# SpeedOfLightController.net
KiCad netlist of a schematic drawn in EAGLE
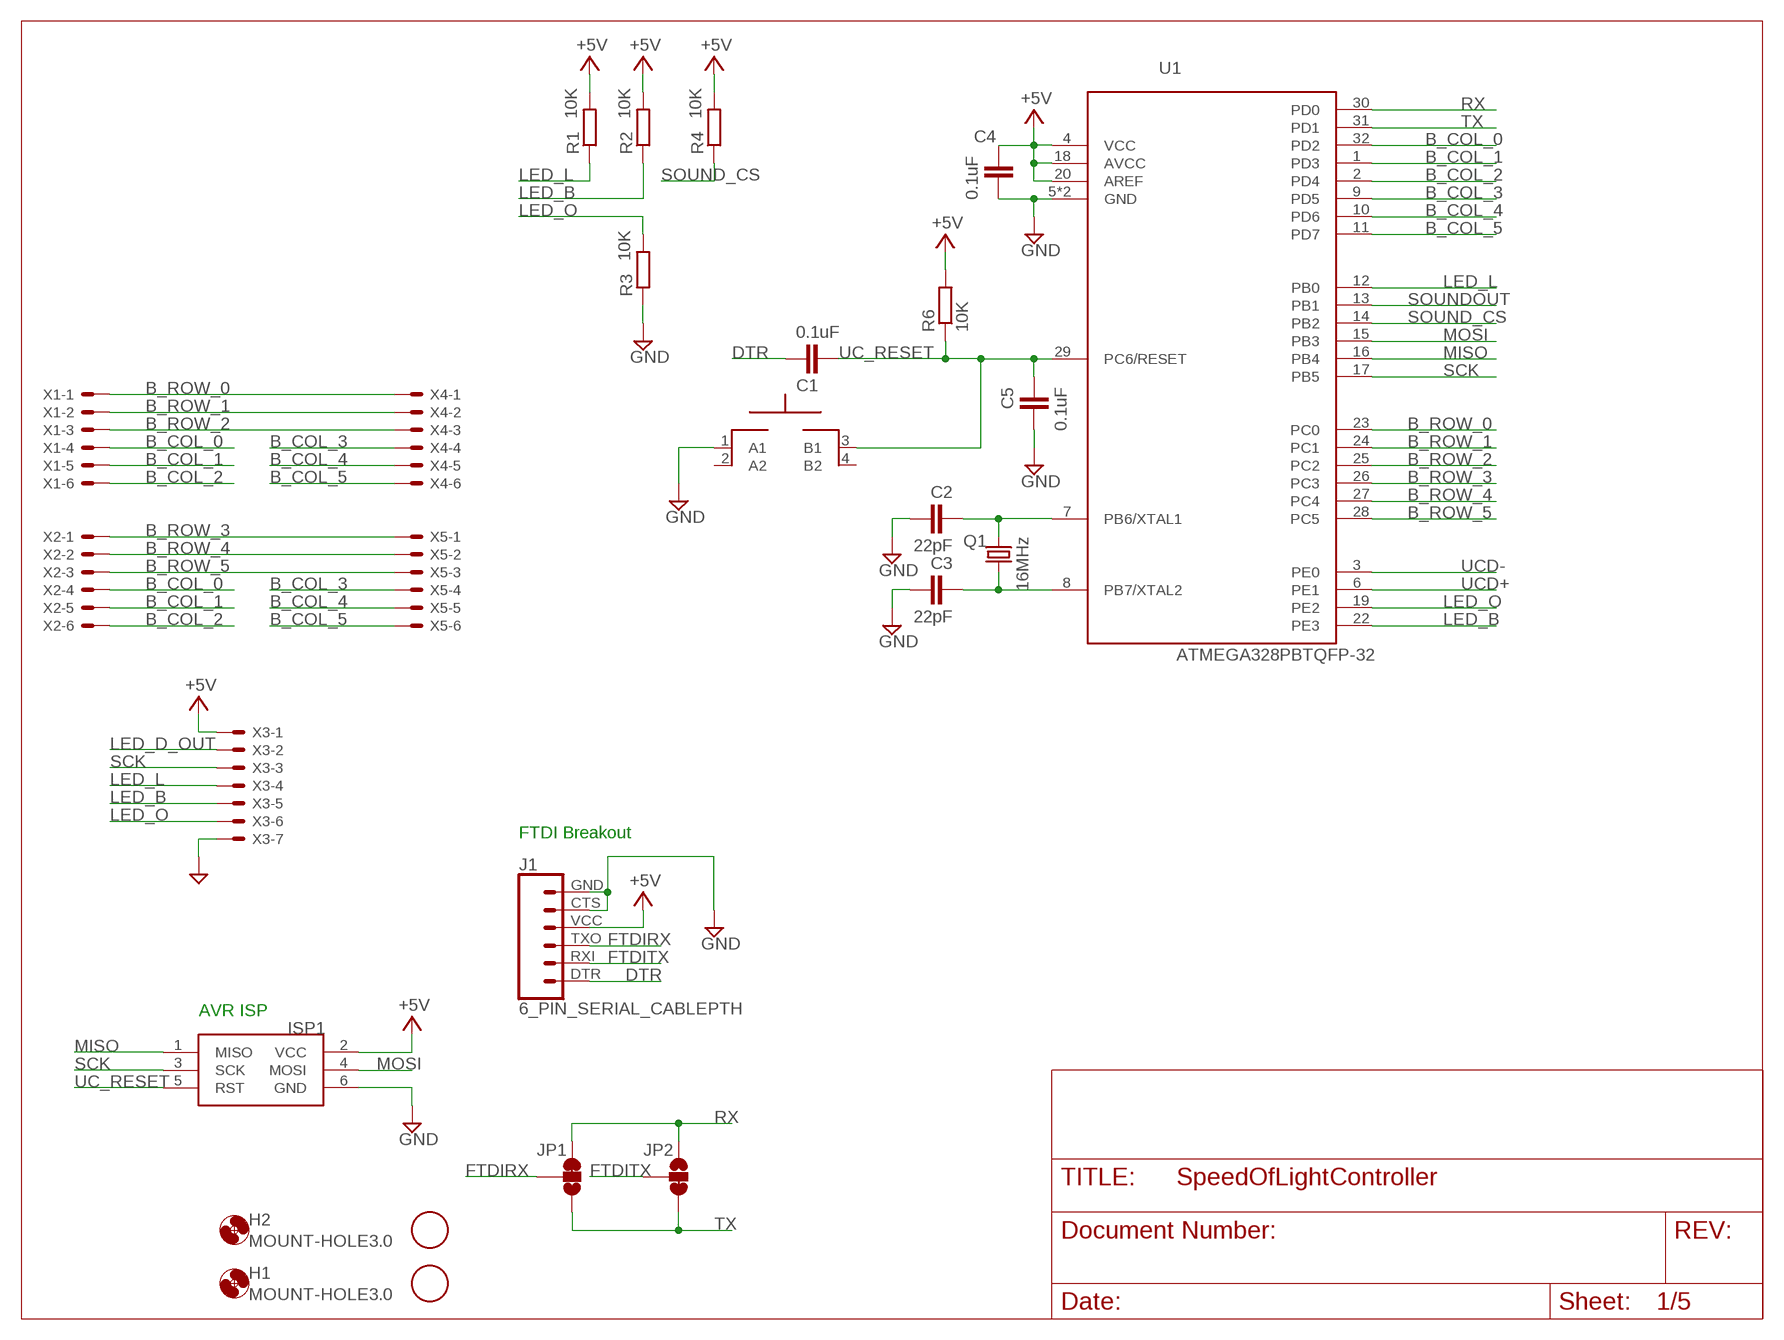
[diagram p0: schematic, sheet 1]
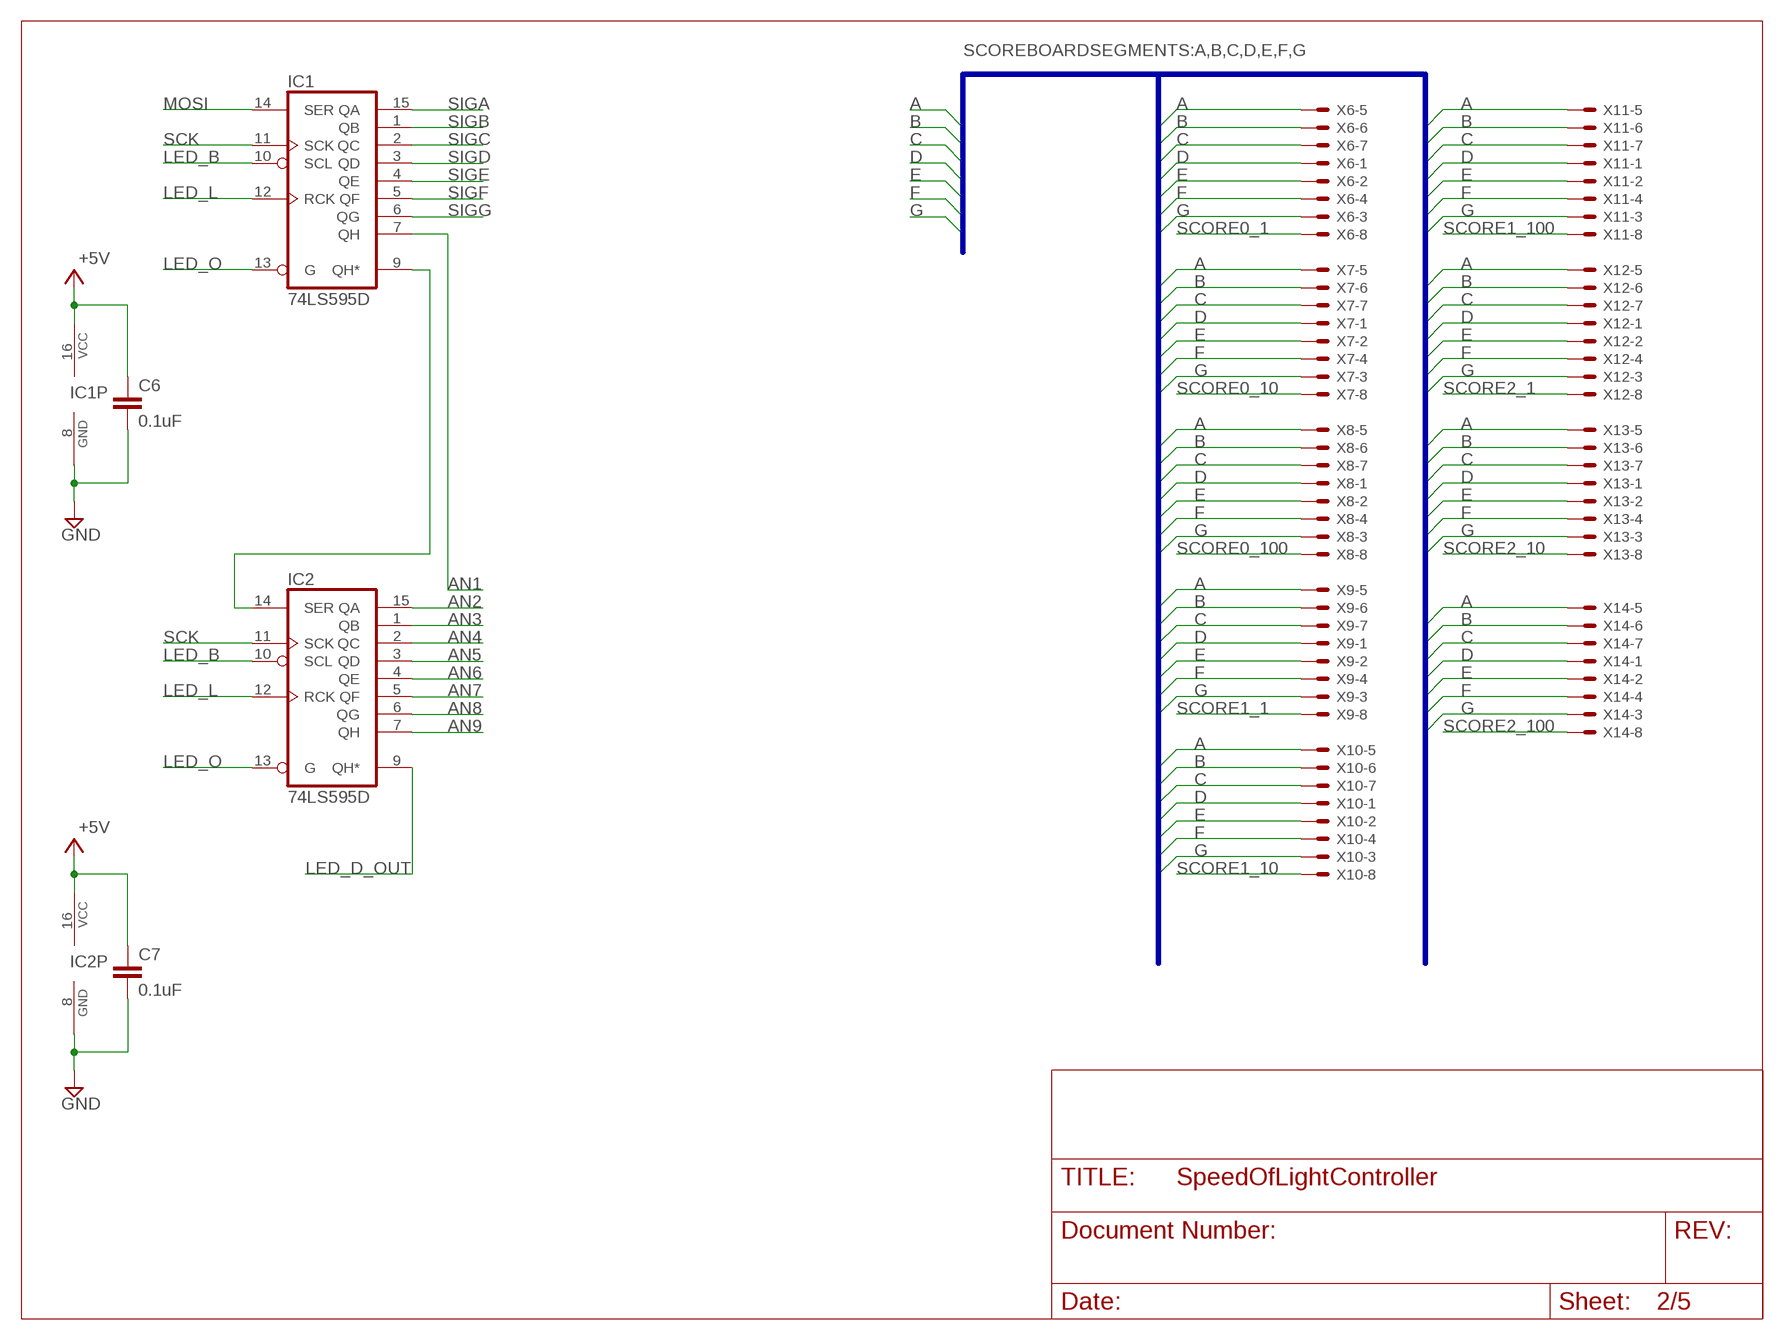
[diagram p1: schematic, sheet 2]
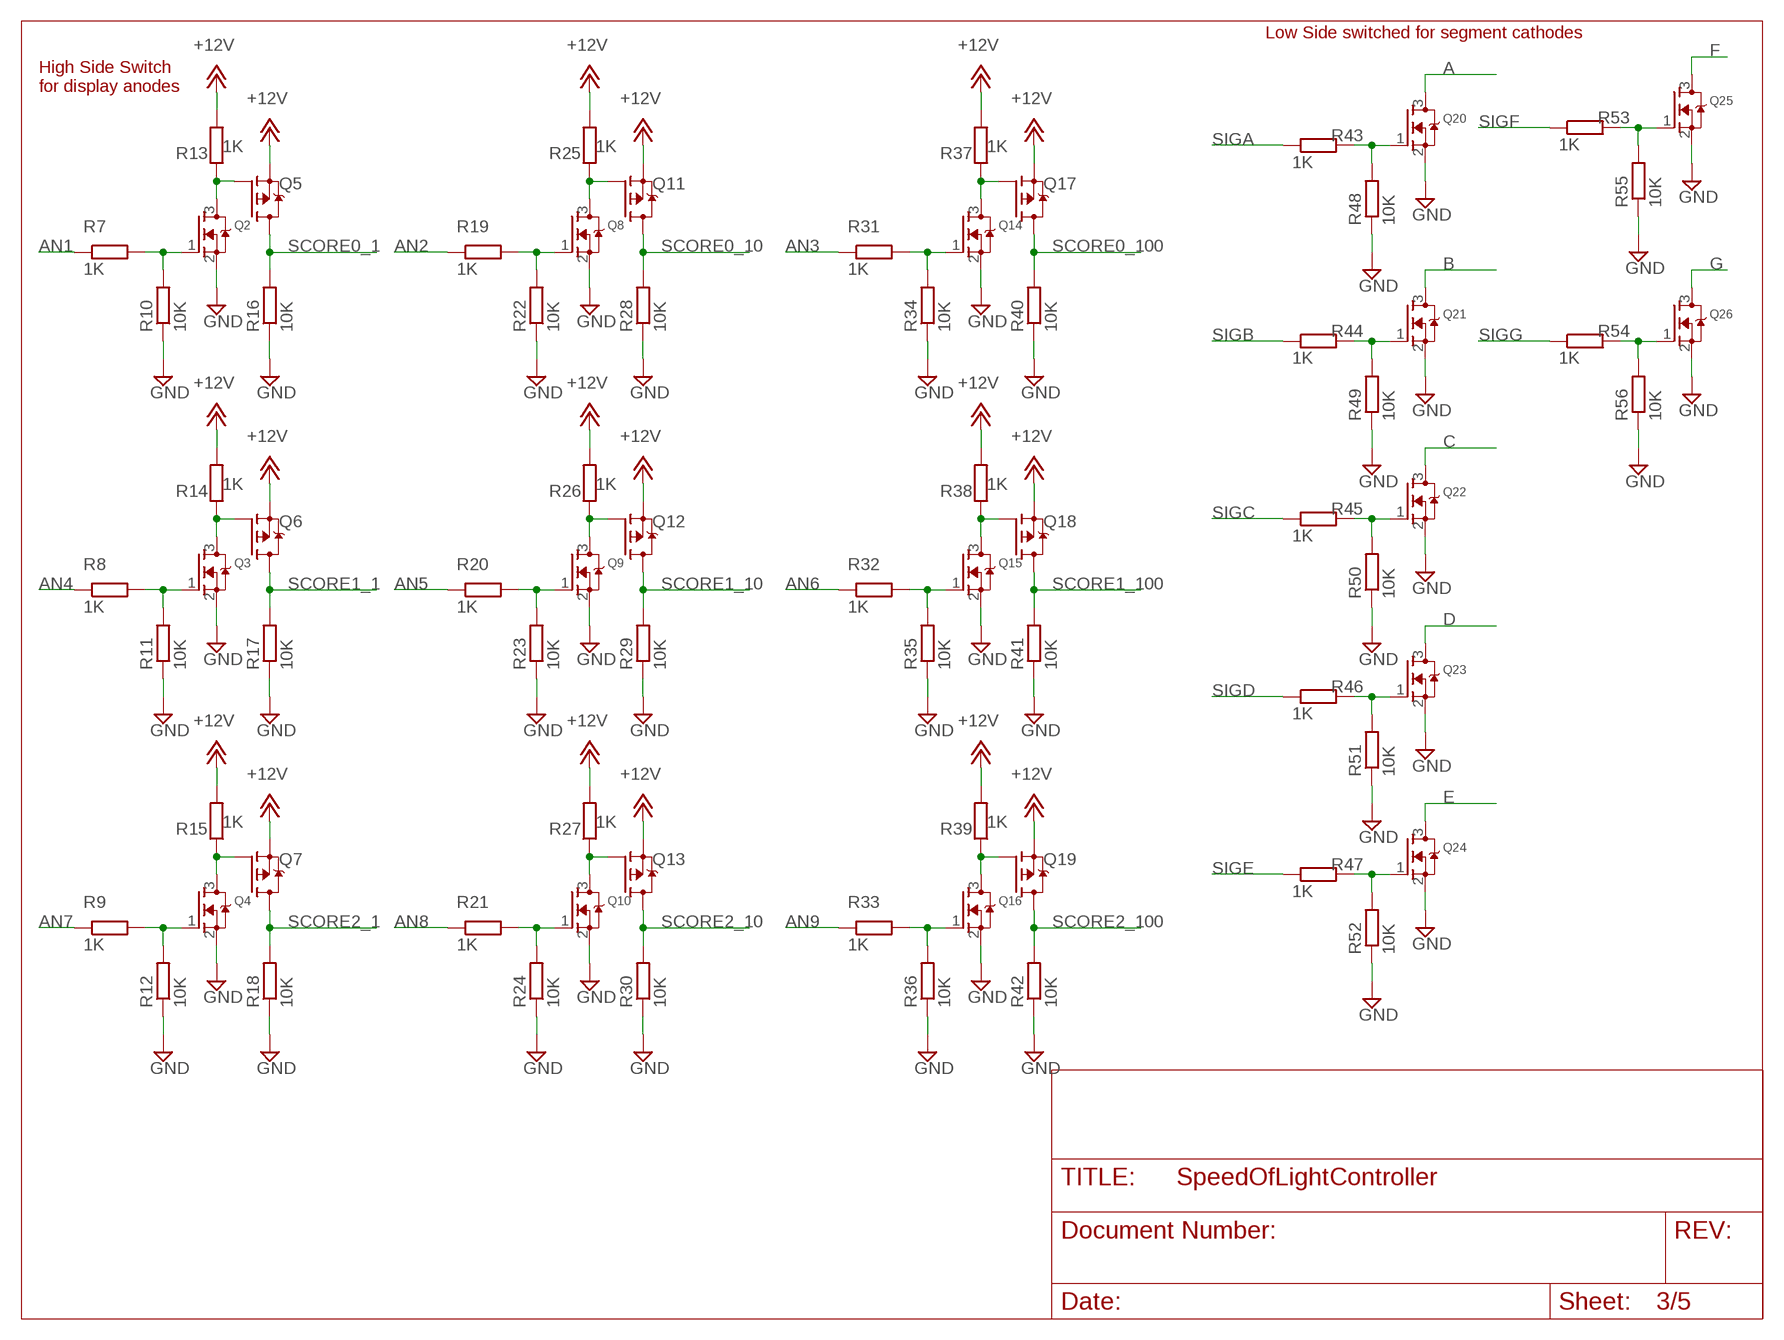
[diagram p2: schematic, sheet 3]
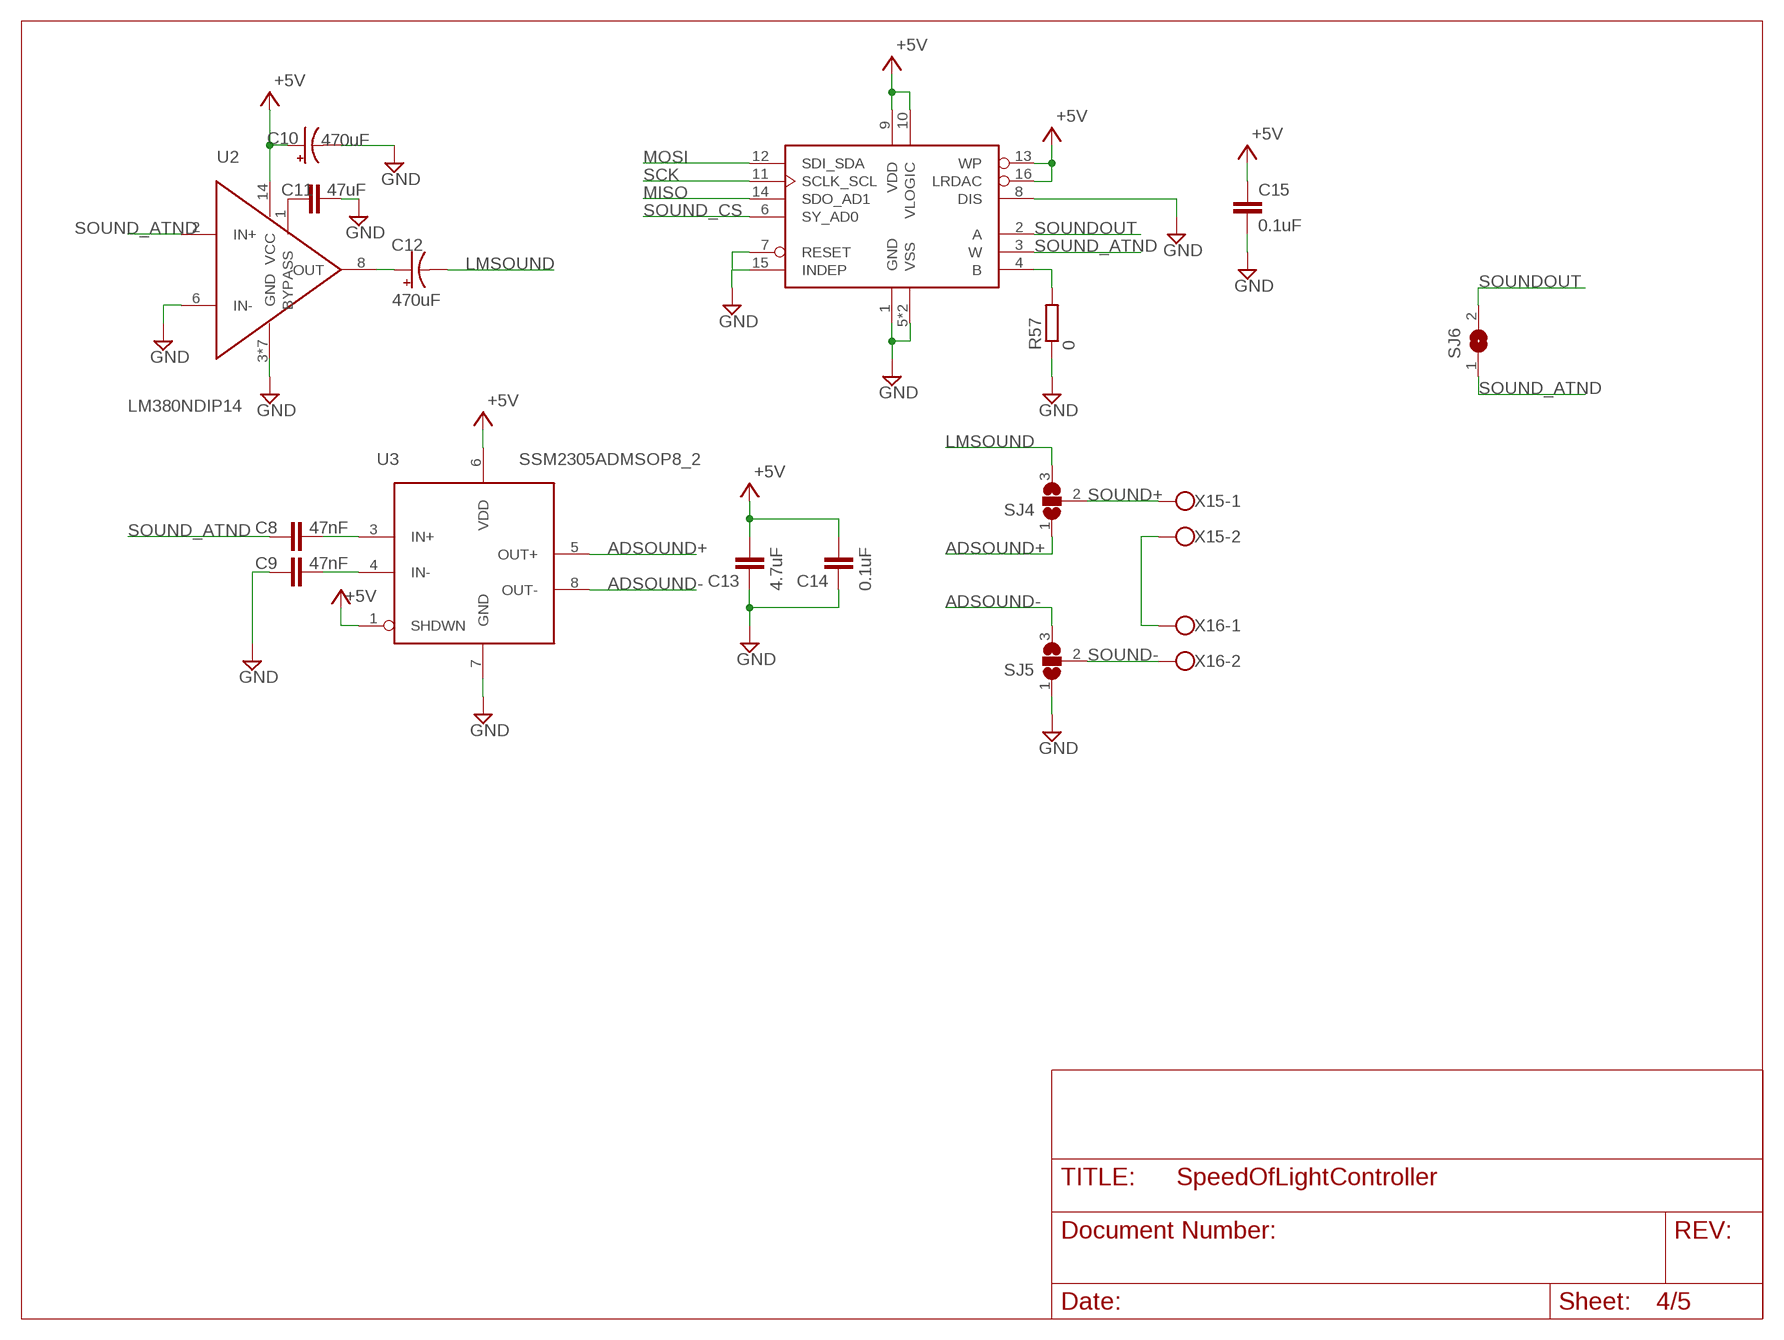
[diagram p3: schematic, sheet 4]
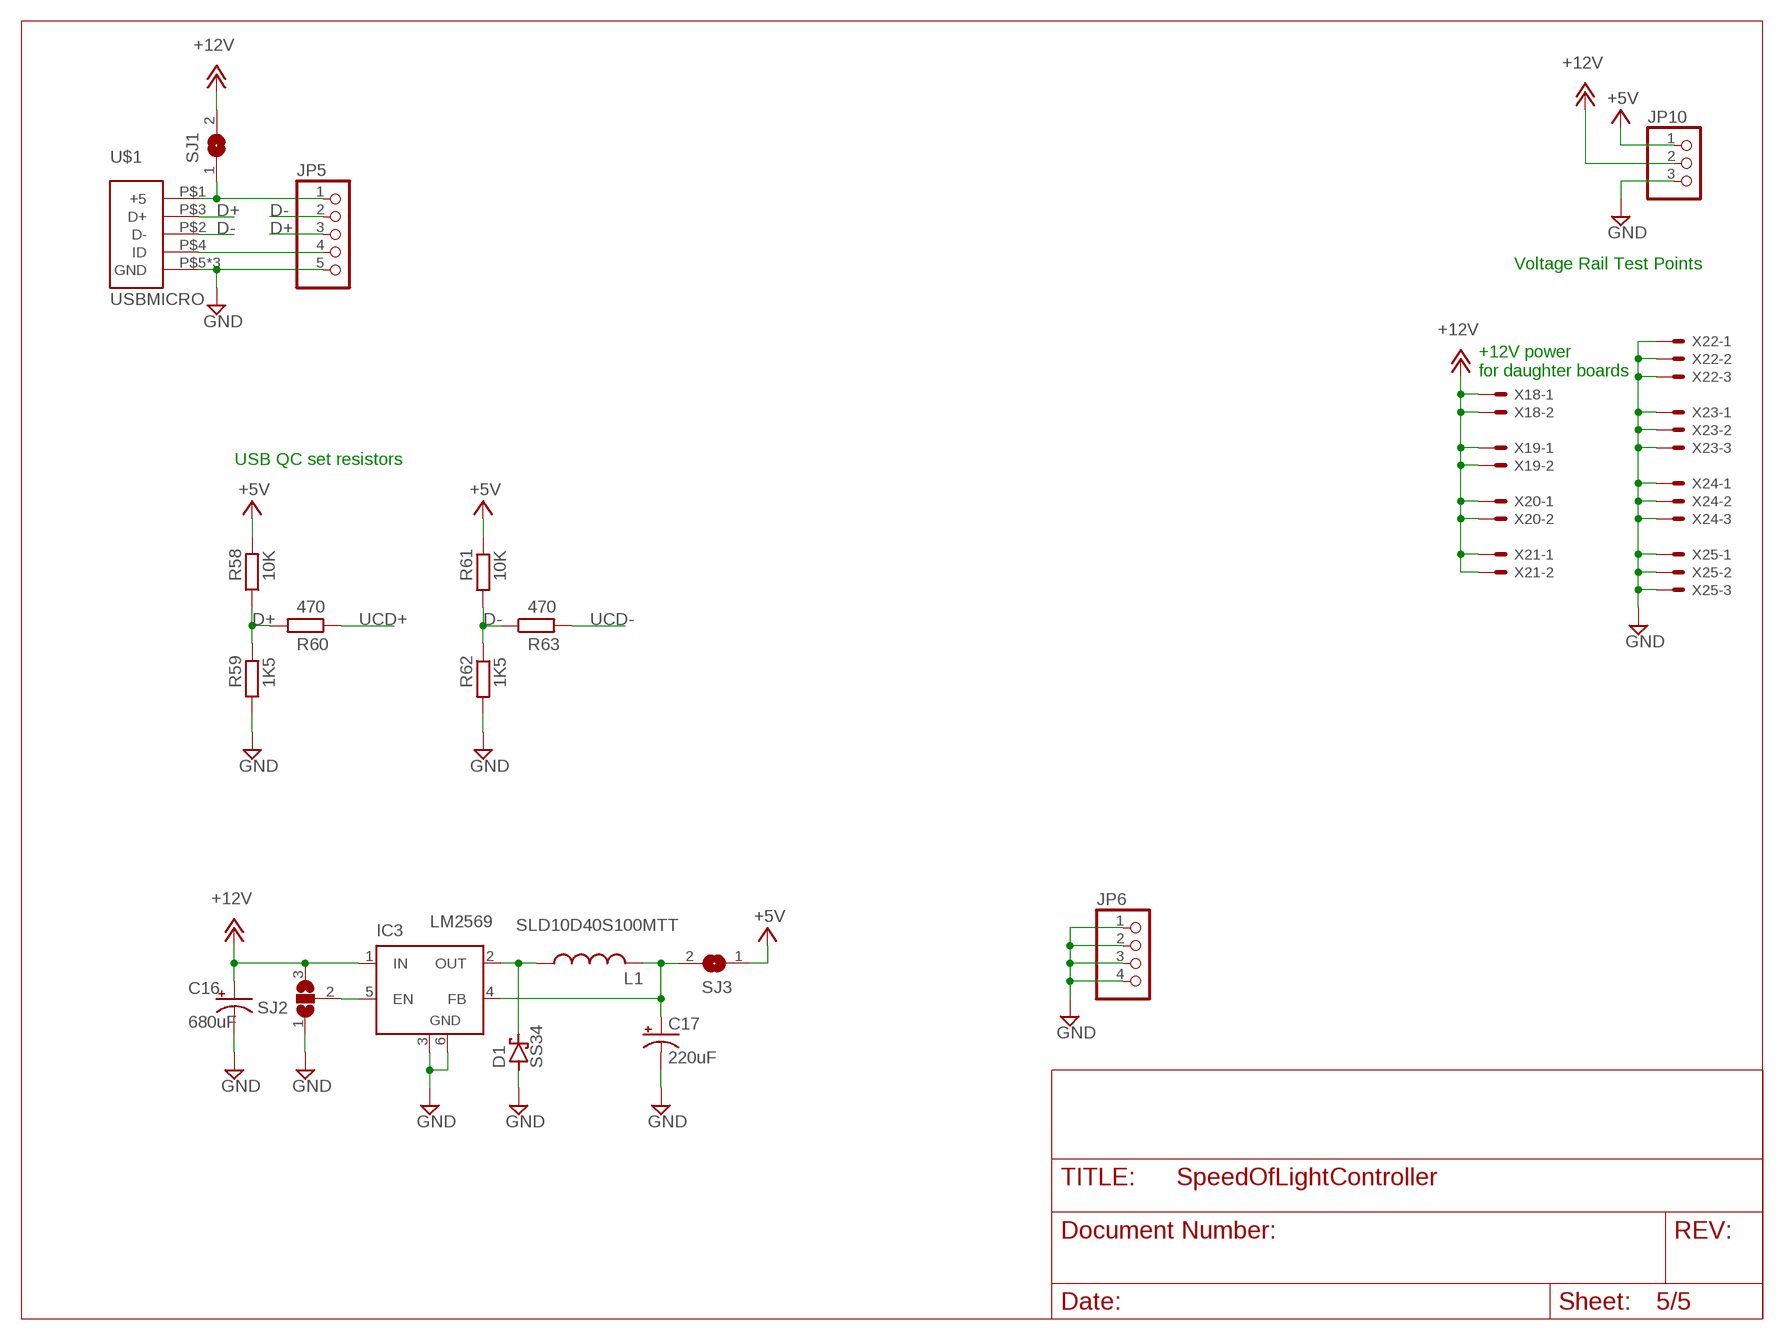
[diagram p4: schematic, sheet 5]

(export (version "E")
  (design (tool "Eeschema 10.0.6"))
  (components
    (comp (ref "C6")
      (value "0.1uF")
      (footprint "eagle-import:C0805")
      (libsource (lib "eagle-import") (part "C-EUC0805"))
    )
    (comp (ref "C7")
      (value "0.1uF")
      (footprint "eagle-import:C0805")
      (libsource (lib "eagle-import") (part "C-EUC0805"))
    )
    (comp (ref "IC1")
      (value "74LS595D")
      (footprint "eagle-import:SO16")
      (libsource (lib "eagle-import") (part "74595DLS"))
    )
    (comp (ref "IC2")
      (value "74LS595D")
      (footprint "eagle-import:SO16")
      (libsource (lib "eagle-import") (part "74595DLS"))
    )
    (comp (ref "X6")
      (value "JST-XH-08-PIN-LONG-PAD")
      (footprint "eagle-import:JST-XH-08-PACKAGE-LONG-PAD")
      (libsource (lib "eagle-import") (part "JST-XH-08-PIN-LONG-PAD"))
    )
    (comp (ref "X7")
      (value "JST-XH-08-PIN-LONG-PAD")
      (footprint "eagle-import:JST-XH-08-PACKAGE-LONG-PAD")
      (libsource (lib "eagle-import") (part "JST-XH-08-PIN-LONG-PAD"))
    )
    (comp (ref "X8")
      (value "JST-XH-08-PIN-LONG-PAD")
      (footprint "eagle-import:JST-XH-08-PACKAGE-LONG-PAD")
      (libsource (lib "eagle-import") (part "JST-XH-08-PIN-LONG-PAD"))
    )
    (comp (ref "X9")
      (value "JST-XH-08-PIN-LONG-PAD")
      (footprint "eagle-import:JST-XH-08-PACKAGE-LONG-PAD")
      (libsource (lib "eagle-import") (part "JST-XH-08-PIN-LONG-PAD"))
    )
    (comp (ref "X10")
      (value "JST-XH-08-PIN-LONG-PAD")
      (footprint "eagle-import:JST-XH-08-PACKAGE-LONG-PAD")
      (libsource (lib "eagle-import") (part "JST-XH-08-PIN-LONG-PAD"))
    )
    (comp (ref "X11")
      (value "JST-XH-08-PIN-LONG-PAD")
      (footprint "eagle-import:JST-XH-08-PACKAGE-LONG-PAD")
      (libsource (lib "eagle-import") (part "JST-XH-08-PIN-LONG-PAD"))
    )
    (comp (ref "X12")
      (value "JST-XH-08-PIN-LONG-PAD")
      (footprint "eagle-import:JST-XH-08-PACKAGE-LONG-PAD")
      (libsource (lib "eagle-import") (part "JST-XH-08-PIN-LONG-PAD"))
    )
    (comp (ref "X13")
      (value "JST-XH-08-PIN-LONG-PAD")
      (footprint "eagle-import:JST-XH-08-PACKAGE-LONG-PAD")
      (libsource (lib "eagle-import") (part "JST-XH-08-PIN-LONG-PAD"))
    )
    (comp (ref "X14")
      (value "JST-XH-08-PIN-LONG-PAD")
      (footprint "eagle-import:JST-XH-08-PACKAGE-LONG-PAD")
      (libsource (lib "eagle-import") (part "JST-XH-08-PIN-LONG-PAD"))
    )
    (comp (ref "Q2")
      (value "AO3414SOT23")
      (footprint "eagle-import:SOT95P240X110-3N")
      (libsource (lib "eagle-import") (part "AO3414SOT23"))
    )
    (comp (ref "Q3")
      (value "AO3414SOT23")
      (footprint "eagle-import:SOT95P240X110-3N")
      (libsource (lib "eagle-import") (part "AO3414SOT23"))
    )
    (comp (ref "Q4")
      (value "AO3414SOT23")
      (footprint "eagle-import:SOT95P240X110-3N")
      (libsource (lib "eagle-import") (part "AO3414SOT23"))
    )
    (comp (ref "Q5")
      (value "AO3415")
      (footprint "eagle-import:SOT95P240X110-3N")
      (libsource (lib "eagle-import") (part "AO3415"))
    )
    (comp (ref "Q6")
      (value "AO3415")
      (footprint "eagle-import:SOT95P240X110-3N")
      (libsource (lib "eagle-import") (part "AO3415"))
    )
    (comp (ref "Q7")
      (value "AO3415")
      (footprint "eagle-import:SOT95P240X110-3N")
      (libsource (lib "eagle-import") (part "AO3415"))
    )
    (comp (ref "Q8")
      (value "AO3414SOT23")
      (footprint "eagle-import:SOT95P240X110-3N")
      (libsource (lib "eagle-import") (part "AO3414SOT23"))
    )
    (comp (ref "Q9")
      (value "AO3414SOT23")
      (footprint "eagle-import:SOT95P240X110-3N")
      (libsource (lib "eagle-import") (part "AO3414SOT23"))
    )
    (comp (ref "Q10")
      (value "AO3414SOT23")
      (footprint "eagle-import:SOT95P240X110-3N")
      (libsource (lib "eagle-import") (part "AO3414SOT23"))
    )
    (comp (ref "Q11")
      (value "AO3415")
      (footprint "eagle-import:SOT95P240X110-3N")
      (libsource (lib "eagle-import") (part "AO3415"))
    )
    (comp (ref "Q12")
      (value "AO3415")
      (footprint "eagle-import:SOT95P240X110-3N")
      (libsource (lib "eagle-import") (part "AO3415"))
    )
    (comp (ref "Q13")
      (value "AO3415")
      (footprint "eagle-import:SOT95P240X110-3N")
      (libsource (lib "eagle-import") (part "AO3415"))
    )
    (comp (ref "Q14")
      (value "AO3414SOT23")
      (footprint "eagle-import:SOT95P240X110-3N")
      (libsource (lib "eagle-import") (part "AO3414SOT23"))
    )
    (comp (ref "Q15")
      (value "AO3414SOT23")
      (footprint "eagle-import:SOT95P240X110-3N")
      (libsource (lib "eagle-import") (part "AO3414SOT23"))
    )
    (comp (ref "Q16")
      (value "AO3414SOT23")
      (footprint "eagle-import:SOT95P240X110-3N")
      (libsource (lib "eagle-import") (part "AO3414SOT23"))
    )
    (comp (ref "Q17")
      (value "AO3415")
      (footprint "eagle-import:SOT95P240X110-3N")
      (libsource (lib "eagle-import") (part "AO3415"))
    )
    (comp (ref "Q18")
      (value "AO3415")
      (footprint "eagle-import:SOT95P240X110-3N")
      (libsource (lib "eagle-import") (part "AO3415"))
    )
    (comp (ref "Q19")
      (value "AO3415")
      (footprint "eagle-import:SOT95P240X110-3N")
      (libsource (lib "eagle-import") (part "AO3415"))
    )
    (comp (ref "Q20")
      (value "AO3414SOT23")
      (footprint "eagle-import:SOT95P240X110-3N")
      (libsource (lib "eagle-import") (part "AO3414SOT23"))
    )
    (comp (ref "Q21")
      (value "AO3414SOT23")
      (footprint "eagle-import:SOT95P240X110-3N")
      (libsource (lib "eagle-import") (part "AO3414SOT23"))
    )
    (comp (ref "Q22")
      (value "AO3414SOT23")
      (footprint "eagle-import:SOT95P240X110-3N")
      (libsource (lib "eagle-import") (part "AO3414SOT23"))
    )
    (comp (ref "Q23")
      (value "AO3414SOT23")
      (footprint "eagle-import:SOT95P240X110-3N")
      (libsource (lib "eagle-import") (part "AO3414SOT23"))
    )
    (comp (ref "Q24")
      (value "AO3414SOT23")
      (footprint "eagle-import:SOT95P240X110-3N")
      (libsource (lib "eagle-import") (part "AO3414SOT23"))
    )
    (comp (ref "Q25")
      (value "AO3414SOT23")
      (footprint "eagle-import:SOT95P240X110-3N")
      (libsource (lib "eagle-import") (part "AO3414SOT23"))
    )
    (comp (ref "Q26")
      (value "AO3414SOT23")
      (footprint "eagle-import:SOT95P240X110-3N")
      (libsource (lib "eagle-import") (part "AO3414SOT23"))
    )
    (comp (ref "R7")
      (value "1K")
      (footprint "eagle-import:R0805")
      (libsource (lib "eagle-import") (part "R-EU_R0805"))
    )
    (comp (ref "R8")
      (value "1K")
      (footprint "eagle-import:R0805")
      (libsource (lib "eagle-import") (part "R-EU_R0805"))
    )
    (comp (ref "R9")
      (value "1K")
      (footprint "eagle-import:R0805")
      (libsource (lib "eagle-import") (part "R-EU_R0805"))
    )
    (comp (ref "R10")
      (value "10K")
      (footprint "eagle-import:R0805")
      (libsource (lib "eagle-import") (part "R-EU_R0805"))
    )
    (comp (ref "R11")
      (value "10K")
      (footprint "eagle-import:R0805")
      (libsource (lib "eagle-import") (part "R-EU_R0805"))
    )
    (comp (ref "R12")
      (value "10K")
      (footprint "eagle-import:R0805")
      (libsource (lib "eagle-import") (part "R-EU_R0805"))
    )
    (comp (ref "R13")
      (value "1K")
      (footprint "eagle-import:R0805")
      (libsource (lib "eagle-import") (part "R-EU_R0805"))
    )
    (comp (ref "R14")
      (value "1K")
      (footprint "eagle-import:R0805")
      (libsource (lib "eagle-import") (part "R-EU_R0805"))
    )
    (comp (ref "R15")
      (value "1K")
      (footprint "eagle-import:R0805")
      (libsource (lib "eagle-import") (part "R-EU_R0805"))
    )
    (comp (ref "R16")
      (value "10K")
      (footprint "eagle-import:R0805")
      (libsource (lib "eagle-import") (part "R-EU_R0805"))
    )
    (comp (ref "R17")
      (value "10K")
      (footprint "eagle-import:R0805")
      (libsource (lib "eagle-import") (part "R-EU_R0805"))
    )
    (comp (ref "R18")
      (value "10K")
      (footprint "eagle-import:R0805")
      (libsource (lib "eagle-import") (part "R-EU_R0805"))
    )
    (comp (ref "R19")
      (value "1K")
      (footprint "eagle-import:R0805")
      (libsource (lib "eagle-import") (part "R-EU_R0805"))
    )
    (comp (ref "R20")
      (value "1K")
      (footprint "eagle-import:R0805")
      (libsource (lib "eagle-import") (part "R-EU_R0805"))
    )
    (comp (ref "R21")
      (value "1K")
      (footprint "eagle-import:R0805")
      (libsource (lib "eagle-import") (part "R-EU_R0805"))
    )
    (comp (ref "R22")
      (value "10K")
      (footprint "eagle-import:R0805")
      (libsource (lib "eagle-import") (part "R-EU_R0805"))
    )
    (comp (ref "R23")
      (value "10K")
      (footprint "eagle-import:R0805")
      (libsource (lib "eagle-import") (part "R-EU_R0805"))
    )
    (comp (ref "R24")
      (value "10K")
      (footprint "eagle-import:R0805")
      (libsource (lib "eagle-import") (part "R-EU_R0805"))
    )
    (comp (ref "R25")
      (value "1K")
      (footprint "eagle-import:R0805")
      (libsource (lib "eagle-import") (part "R-EU_R0805"))
    )
    (comp (ref "R26")
      (value "1K")
      (footprint "eagle-import:R0805")
      (libsource (lib "eagle-import") (part "R-EU_R0805"))
    )
    (comp (ref "R27")
      (value "1K")
      (footprint "eagle-import:R0805")
      (libsource (lib "eagle-import") (part "R-EU_R0805"))
    )
    (comp (ref "R28")
      (value "10K")
      (footprint "eagle-import:R0805")
      (libsource (lib "eagle-import") (part "R-EU_R0805"))
    )
    (comp (ref "R29")
      (value "10K")
      (footprint "eagle-import:R0805")
      (libsource (lib "eagle-import") (part "R-EU_R0805"))
    )
    (comp (ref "R30")
      (value "10K")
      (footprint "eagle-import:R0805")
      (libsource (lib "eagle-import") (part "R-EU_R0805"))
    )
    (comp (ref "R31")
      (value "1K")
      (footprint "eagle-import:R0805")
      (libsource (lib "eagle-import") (part "R-EU_R0805"))
    )
    (comp (ref "R32")
      (value "1K")
      (footprint "eagle-import:R0805")
      (libsource (lib "eagle-import") (part "R-EU_R0805"))
    )
    (comp (ref "R33")
      (value "1K")
      (footprint "eagle-import:R0805")
      (libsource (lib "eagle-import") (part "R-EU_R0805"))
    )
    (comp (ref "R34")
      (value "10K")
      (footprint "eagle-import:R0805")
      (libsource (lib "eagle-import") (part "R-EU_R0805"))
    )
    (comp (ref "R35")
      (value "10K")
      (footprint "eagle-import:R0805")
      (libsource (lib "eagle-import") (part "R-EU_R0805"))
    )
    (comp (ref "R36")
      (value "10K")
      (footprint "eagle-import:R0805")
      (libsource (lib "eagle-import") (part "R-EU_R0805"))
    )
    (comp (ref "R37")
      (value "1K")
      (footprint "eagle-import:R0805")
      (libsource (lib "eagle-import") (part "R-EU_R0805"))
    )
    (comp (ref "R38")
      (value "1K")
      (footprint "eagle-import:R0805")
      (libsource (lib "eagle-import") (part "R-EU_R0805"))
    )
    (comp (ref "R39")
      (value "1K")
      (footprint "eagle-import:R0805")
      (libsource (lib "eagle-import") (part "R-EU_R0805"))
    )
    (comp (ref "R40")
      (value "10K")
      (footprint "eagle-import:R0805")
      (libsource (lib "eagle-import") (part "R-EU_R0805"))
    )
    (comp (ref "R41")
      (value "10K")
      (footprint "eagle-import:R0805")
      (libsource (lib "eagle-import") (part "R-EU_R0805"))
    )
    (comp (ref "R42")
      (value "10K")
      (footprint "eagle-import:R0805")
      (libsource (lib "eagle-import") (part "R-EU_R0805"))
    )
    (comp (ref "R43")
      (value "1K")
      (footprint "eagle-import:R0805")
      (libsource (lib "eagle-import") (part "R-EU_R0805"))
    )
    (comp (ref "R44")
      (value "1K")
      (footprint "eagle-import:R0805")
      (libsource (lib "eagle-import") (part "R-EU_R0805"))
    )
    (comp (ref "R45")
      (value "1K")
      (footprint "eagle-import:R0805")
      (libsource (lib "eagle-import") (part "R-EU_R0805"))
    )
    (comp (ref "R46")
      (value "1K")
      (footprint "eagle-import:R0805")
      (libsource (lib "eagle-import") (part "R-EU_R0805"))
    )
    (comp (ref "R47")
      (value "1K")
      (footprint "eagle-import:R0805")
      (libsource (lib "eagle-import") (part "R-EU_R0805"))
    )
    (comp (ref "R48")
      (value "10K")
      (footprint "eagle-import:R0805")
      (libsource (lib "eagle-import") (part "R-EU_R0805"))
    )
    (comp (ref "R49")
      (value "10K")
      (footprint "eagle-import:R0805")
      (libsource (lib "eagle-import") (part "R-EU_R0805"))
    )
    (comp (ref "R50")
      (value "10K")
      (footprint "eagle-import:R0805")
      (libsource (lib "eagle-import") (part "R-EU_R0805"))
    )
    (comp (ref "R51")
      (value "10K")
      (footprint "eagle-import:R0805")
      (libsource (lib "eagle-import") (part "R-EU_R0805"))
    )
    (comp (ref "R52")
      (value "10K")
      (footprint "eagle-import:R0805")
      (libsource (lib "eagle-import") (part "R-EU_R0805"))
    )
    (comp (ref "R53")
      (value "1K")
      (footprint "eagle-import:R0805")
      (libsource (lib "eagle-import") (part "R-EU_R0805"))
    )
    (comp (ref "R54")
      (value "1K")
      (footprint "eagle-import:R0805")
      (libsource (lib "eagle-import") (part "R-EU_R0805"))
    )
    (comp (ref "R55")
      (value "10K")
      (footprint "eagle-import:R0805")
      (libsource (lib "eagle-import") (part "R-EU_R0805"))
    )
    (comp (ref "R56")
      (value "10K")
      (footprint "eagle-import:R0805")
      (libsource (lib "eagle-import") (part "R-EU_R0805"))
    )
    (comp (ref "C8")
      (value "47nF")
      (footprint "eagle-import:C0805")
      (libsource (lib "eagle-import") (part "C-EUC0805"))
    )
    (comp (ref "C9")
      (value "47nF")
      (footprint "eagle-import:C0805")
      (libsource (lib "eagle-import") (part "C-EUC0805"))
    )
    (comp (ref "C10")
      (value "470uF")
      (footprint "eagle-import:140CLH-0810")
      (libsource (lib "eagle-import") (part "CPOL-US140CLH-0810"))
    )
    (comp (ref "C11")
      (value "47uF")
      (footprint "eagle-import:C0805")
      (libsource (lib "eagle-import") (part "C-EUC0805"))
    )
    (comp (ref "C12")
      (value "470uF")
      (footprint "eagle-import:140CLH-0810")
      (libsource (lib "eagle-import") (part "CPOL-US140CLH-0810"))
    )
    (comp (ref "C13")
      (value "4.7uF")
      (footprint "eagle-import:C0805")
      (libsource (lib "eagle-import") (part "C-EUC0805"))
    )
    (comp (ref "C14")
      (value "0.1uF")
      (footprint "eagle-import:C0805")
      (libsource (lib "eagle-import") (part "C-EUC0805"))
    )
    (comp (ref "C15")
      (value "0.1uF")
      (footprint "eagle-import:C0805")
      (libsource (lib "eagle-import") (part "C-EUC0805"))
    )
    (comp (ref "R57")
      (value "0")
      (footprint "eagle-import:R0805W")
      (libsource (lib "eagle-import") (part "R-EU_R0805W"))
    )
    (comp (ref "SJ4")
      (value "SJ2W")
      (footprint "eagle-import:SJ_2")
      (libsource (lib "eagle-import") (part "SJ2W"))
    )
    (comp (ref "SJ5")
      (value "SJ2W")
      (footprint "eagle-import:SJ_2")
      (libsource (lib "eagle-import") (part "SJ2W"))
    )
    (comp (ref "SJ6") (value "SJ") (footprint "eagle-import:SJ") (libsource (lib "eagle-import") (part "SJ")))
    (comp (ref "U2")
      (value "LM380NDIP14")
      (footprint "eagle-import:DIP762W53P254L1969H508Q14B")
      (libsource (lib "eagle-import") (part "LM380NDIP14"))
    )
    (comp (ref "U3")
      (value "SSM2305ADMSOP8_2")
      (footprint "eagle-import:SOP65P490X95-8N")
      (libsource (lib "eagle-import") (part "SSM2305ADMSOP8_2"))
    )
    (comp (ref "U4")
      (value "AD5141ADLFCSP3")
      (footprint "eagle-import:QFN50P300X300X80-17T160N")
      (libsource (lib "eagle-import") (part "AD5141ADLFCSP3"))
    )
    (comp (ref "X15")
      (value "1X02_5MM_SCREW")
      (footprint "eagle-import:W237-102")
      (fields (field (name "MPN") "237-102"))
      (libsource (lib "eagle-import") (part "1X02_5MM_SCREW"))
    )
    (comp (ref "X16")
      (value "1X02_5MM_SCREW")
      (footprint "eagle-import:W237-102")
      (fields (field (name "MPN") "237-102"))
      (libsource (lib "eagle-import") (part "1X02_5MM_SCREW"))
    )
    (comp (ref "C1")
      (value "0.1uF")
      (footprint "eagle-import:C0805")
      (libsource (lib "eagle-import") (part "C-EUC0805"))
    )
    (comp (ref "C2")
      (value "22pF")
      (footprint "eagle-import:C0805")
      (libsource (lib "eagle-import") (part "C-EUC0805"))
    )
    (comp (ref "C3")
      (value "22pF")
      (footprint "eagle-import:C0805")
      (libsource (lib "eagle-import") (part "C-EUC0805"))
    )
    (comp (ref "C4")
      (value "0.1uF")
      (footprint "eagle-import:C0805")
      (libsource (lib "eagle-import") (part "C-EUC0805"))
    )
    (comp (ref "C5")
      (value "0.1uF")
      (footprint "eagle-import:C0805")
      (libsource (lib "eagle-import") (part "C-EUC0805"))
    )
    (comp (ref "F1")
      (value "FIDUCIAL")
      (footprint "eagle-import:FIDUCIAL_1MM")
      (libsource (lib "eagle-import") (part "FIDUCIAL"))
    )
    (comp (ref "F2")
      (value "FIDUCIAL")
      (footprint "eagle-import:FIDUCIAL_1MM")
      (libsource (lib "eagle-import") (part "FIDUCIAL"))
    )
    (comp (ref "H1")
      (value "MOUNT-HOLE3.0")
      (footprint "eagle-import:3,0")
      (libsource (lib "eagle-import") (part "MOUNT-HOLE3.0"))
    )
    (comp (ref "H2")
      (value "MOUNT-HOLE3.0")
      (footprint "eagle-import:3,0")
      (libsource (lib "eagle-import") (part "MOUNT-HOLE3.0"))
    )
    (comp (ref "ISP1")
      (value "AVRISP-6")
      (footprint "eagle-import:AVRISP")
      (libsource (lib "eagle-import") (part "AVRISP-6"))
    )
    (comp (ref "J1")
      (value "6_PIN_SERIAL_CABLEPTH")
      (footprint "eagle-import:FTDI_BASIC")
      (libsource (lib "eagle-import") (part "6_PIN_SERIAL_CABLEPTH"))
    )
    (comp (ref "JP1")
      (value "JUMPER-SMT_3_1-NC_TRACE_SILK")
      (footprint "eagle-import:SMT-JUMPER_3_1-NC_TRACE_SILK")
      (libsource (lib "eagle-import") (part "JUMPER-SMT_3_1-NC_TRACE_SILK"))
    )
    (comp (ref "JP2")
      (value "JUMPER-SMT_3_1-NC_TRACE_SILK")
      (footprint "eagle-import:SMT-JUMPER_3_1-NC_TRACE_SILK")
      (libsource (lib "eagle-import") (part "JUMPER-SMT_3_1-NC_TRACE_SILK"))
    )
    (comp (ref "Q1")
      (value "16MHz")
      (footprint "eagle-import:HC49UP")
      (libsource (lib "eagle-import") (part "CRYSTALHC49UP"))
    )
    (comp (ref "R1")
      (value "10K")
      (footprint "eagle-import:R0805")
      (libsource (lib "eagle-import") (part "R-EU_R0805"))
    )
    (comp (ref "R2")
      (value "10K")
      (footprint "eagle-import:R0805")
      (libsource (lib "eagle-import") (part "R-EU_R0805"))
    )
    (comp (ref "R3")
      (value "10K")
      (footprint "eagle-import:R0805")
      (libsource (lib "eagle-import") (part "R-EU_R0805"))
    )
    (comp (ref "R4")
      (value "10K")
      (footprint "eagle-import:R0805")
      (libsource (lib "eagle-import") (part "R-EU_R0805"))
    )
    (comp (ref "R6")
      (value "10K")
      (footprint "eagle-import:R0805")
      (libsource (lib "eagle-import") (part "R-EU_R0805"))
    )
    (comp (ref "RESET")
      (value "MOMENTARYBUTTON")
      (footprint "eagle-import:SPST_NO_SMD")
      (libsource (lib "eagle-import") (part "MOMENTARYBUTTON"))
    )
    (comp (ref "U1")
      (value "ATMEGA328PBTQFP-32")
      (footprint "eagle-import:QFP80P900X900X120-32N")
      (libsource (lib "eagle-import") (part "ATMEGA328PBTQFP-32"))
    )
    (comp (ref "X1")
      (value "JST-XH-06-PIN-LONG-PAD")
      (footprint "eagle-import:JST-XH-06-PACKAGE-LONG-PAD")
      (libsource (lib "eagle-import") (part "JST-XH-06-PIN-LONG-PAD"))
    )
    (comp (ref "X2")
      (value "JST-XH-06-PIN-LONG-PAD")
      (footprint "eagle-import:JST-XH-06-PACKAGE-LONG-PAD")
      (libsource (lib "eagle-import") (part "JST-XH-06-PIN-LONG-PAD"))
    )
    (comp (ref "X3")
      (value "JST-XH-07-PIN-LONG-PAD")
      (footprint "eagle-import:JST-XH-07-PACKAGE-LONG-PAD")
      (libsource (lib "eagle-import") (part "JST-XH-07-PIN-LONG-PAD"))
    )
    (comp (ref "X4")
      (value "JST-XH-06-PIN-LONG-PAD")
      (footprint "eagle-import:JST-XH-06-PACKAGE-LONG-PAD")
      (libsource (lib "eagle-import") (part "JST-XH-06-PIN-LONG-PAD"))
    )
    (comp (ref "X5")
      (value "JST-XH-06-PIN-LONG-PAD")
      (footprint "eagle-import:JST-XH-06-PACKAGE-LONG-PAD")
      (libsource (lib "eagle-import") (part "JST-XH-06-PIN-LONG-PAD"))
    )
    (comp (ref "C16")
      (value "680uF")
      (footprint "eagle-import:140CLH-0810")
      (libsource (lib "eagle-import") (part "CPOL-US140CLH-0810"))
    )
    (comp (ref "C17")
      (value "220uF")
      (footprint "eagle-import:140CLH-0810")
      (libsource (lib "eagle-import") (part "CPOL-US140CLH-0810"))
    )
    (comp (ref "D1")
      (value "SS34")
      (footprint "eagle-import:SMA")
      (libsource (lib "eagle-import") (part "SS34"))
    )
    (comp (ref "IC3")
      (value "LM2596S")
      (footprint "eagle-import:TO263-5")
      (libsource (lib "eagle-import") (part "LM2596S"))
    )
    (comp (ref "JP5")
      (value "PINHD-1X5")
      (footprint "eagle-import:1X05")
      (libsource (lib "eagle-import") (part "PINHD-1X5"))
    )
    (comp (ref "JP6")
      (value "PINHD-1X4")
      (footprint "eagle-import:1X04")
      (libsource (lib "eagle-import") (part "PINHD-1X4"))
    )
    (comp (ref "JP10")
      (value "PINHD-1X3")
      (footprint "eagle-import:1X03")
      (libsource (lib "eagle-import") (part "PINHD-1X3"))
    )
    (comp (ref "L1")
      (value "SLD10D40S100MTT")
      (footprint "eagle-import:SMD10.5X10.3")
      (libsource (lib "eagle-import") (part "SLD10D40S100MTT"))
    )
    (comp (ref "R58")
      (value "10K")
      (footprint "eagle-import:R0805")
      (libsource (lib "eagle-import") (part "R-EU_R0805"))
    )
    (comp (ref "R59")
      (value "1K5")
      (footprint "eagle-import:R0805")
      (libsource (lib "eagle-import") (part "R-EU_R0805"))
    )
    (comp (ref "R60")
      (value "470")
      (footprint "eagle-import:R0805")
      (libsource (lib "eagle-import") (part "R-EU_R0805"))
    )
    (comp (ref "R61")
      (value "10K")
      (footprint "eagle-import:R0805")
      (libsource (lib "eagle-import") (part "R-EU_R0805"))
    )
    (comp (ref "R62")
      (value "1K5")
      (footprint "eagle-import:R0805")
      (libsource (lib "eagle-import") (part "R-EU_R0805"))
    )
    (comp (ref "R63")
      (value "470")
      (footprint "eagle-import:R0805")
      (libsource (lib "eagle-import") (part "R-EU_R0805"))
    )
    (comp (ref "SJ1") (value "SJ") (footprint "eagle-import:SJ") (libsource (lib "eagle-import") (part "SJ")))
    (comp (ref "SJ2")
      (value "SJ2WW")
      (footprint "eagle-import:SJ_2W")
      (libsource (lib "eagle-import") (part "SJ2WW"))
    )
    (comp (ref "SJ3") (value "SJ") (footprint "eagle-import:SJ") (libsource (lib "eagle-import") (part "SJ")))
    (comp (ref "U$1")
      (value "USBMICRO")
      (footprint "eagle-import:USBMICRO")
      (libsource (lib "eagle-import") (part "USBMICRO"))
    )
    (comp (ref "X18")
      (value "JST-XH-02-PIN-LONG-PAD")
      (footprint "eagle-import:JST-XH-02-PACKAGE-LONG-PAD")
      (libsource (lib "eagle-import") (part "JST-XH-02-PIN-LONG-PAD"))
    )
    (comp (ref "X19")
      (value "JST-XH-02-PIN-LONG-PAD")
      (footprint "eagle-import:JST-XH-02-PACKAGE-LONG-PAD")
      (libsource (lib "eagle-import") (part "JST-XH-02-PIN-LONG-PAD"))
    )
    (comp (ref "X20")
      (value "JST-XH-02-PIN-LONG-PAD")
      (footprint "eagle-import:JST-XH-02-PACKAGE-LONG-PAD")
      (libsource (lib "eagle-import") (part "JST-XH-02-PIN-LONG-PAD"))
    )
    (comp (ref "X21")
      (value "JST-XH-02-PIN-LONG-PAD")
      (footprint "eagle-import:JST-XH-02-PACKAGE-LONG-PAD")
      (libsource (lib "eagle-import") (part "JST-XH-02-PIN-LONG-PAD"))
    )
    (comp (ref "X22")
      (value "JST-XH-03-PIN-LONG-PAD")
      (footprint "eagle-import:JST-XH-03-PACKAGE-LONG-PAD")
      (libsource (lib "eagle-import") (part "JST-XH-03-PIN-LONG-PAD"))
    )
    (comp (ref "X23")
      (value "JST-XH-03-PIN-LONG-PAD")
      (footprint "eagle-import:JST-XH-03-PACKAGE-LONG-PAD")
      (libsource (lib "eagle-import") (part "JST-XH-03-PIN-LONG-PAD"))
    )
    (comp (ref "X24")
      (value "JST-XH-03-PIN-LONG-PAD")
      (footprint "eagle-import:JST-XH-03-PACKAGE-LONG-PAD")
      (libsource (lib "eagle-import") (part "JST-XH-03-PIN-LONG-PAD"))
    )
    (comp (ref "X25")
      (value "JST-XH-03-PIN-LONG-PAD")
      (footprint "eagle-import:JST-XH-03-PACKAGE-LONG-PAD")
      (libsource (lib "eagle-import") (part "JST-XH-03-PIN-LONG-PAD"))
    )
  )
  (nets
    (net (code "2") (name "+5V") (class "Default")
      (node (ref "C10") (pin "+") (pinfunction "+_+") (pintype "passive"))
      (node (ref "C13") (pin "2") (pinfunction "2_2") (pintype "passive"))
      (node (ref "C14") (pin "2") (pinfunction "2_2") (pintype "passive"))
      (node (ref "C15") (pin "1") (pinfunction "1_1") (pintype "passive"))
      (node (ref "C4") (pin "2") (pinfunction "2_2") (pintype "passive"))
      (node (ref "C6") (pin "1") (pinfunction "1_1") (pintype "passive"))
      (node (ref "C7") (pin "1") (pinfunction "1_1") (pintype "passive"))
      (node (ref "IC1") (pin "16") (pinfunction "VCC_16") (pintype "power_in"))
      (node (ref "IC2") (pin "16") (pinfunction "VCC_16") (pintype "power_in"))
      (node (ref "ISP1") (pin "2") (pinfunction "VCC_2") (pintype "power_in"))
      (node (ref "J1") (pin "VCC") (pinfunction "4_VCC") (pintype "passive"))
      (node (ref "JP10") (pin "1") (pinfunction "1_1") (pintype "passive"))
      (node (ref "R1") (pin "2") (pinfunction "2_2") (pintype "passive"))
      (node (ref "R2") (pin "2") (pinfunction "2_2") (pintype "passive"))
      (node (ref "R4") (pin "2") (pinfunction "2_2") (pintype "passive"))
      (node (ref "R58") (pin "2") (pinfunction "2_2") (pintype "passive"))
      (node (ref "R6") (pin "2") (pinfunction "2_2") (pintype "passive"))
      (node (ref "R61") (pin "1") (pinfunction "1_1") (pintype "passive"))
      (node (ref "SJ3") (pin "1") (pinfunction "1_1") (pintype "passive"))
      (node (ref "U1") (pin "18") (pinfunction "AVCC_18") (pintype "power_in"))
      (node (ref "U1") (pin "20") (pinfunction "AREF_20") (pintype "power_in"))
      (node (ref "U1") (pin "4") (pinfunction "VCC_4") (pintype "power_in"))
      (node (ref "U2") (pin "14") (pinfunction "VCC_14") (pintype "bidirectional"))
      (node (ref "U3") (pin "1") (pinfunction "SHDWN_1") (pintype "bidirectional"))
      (node (ref "U3") (pin "6") (pinfunction "VDD_6") (pintype "bidirectional"))
      (node (ref "U4") (pin "10") (pinfunction "VLOGIC_10") (pintype "bidirectional"))
      (node (ref "U4") (pin "13") (pinfunction "WP_13") (pintype "bidirectional"))
      (node (ref "U4") (pin "16") (pinfunction "LRDAC_16") (pintype "bidirectional"))
      (node (ref "U4") (pin "9") (pinfunction "VDD_9") (pintype "bidirectional"))
      (node (ref "X3") (pin "1") (pinfunction "S_1") (pintype "passive"))
    )
    (net (code "3") (name "+12V") (class "Default")
      (node (ref "C16") (pin "+") (pinfunction "+_+") (pintype "passive"))
      (node (ref "IC3") (pin "1") (pinfunction "IN_1") (pintype "input"))
      (node (ref "JP10") (pin "2") (pinfunction "2_2") (pintype "passive"))
      (node (ref "Q11") (pin "2") (pinfunction "S_2") (pintype "passive"))
      (node (ref "Q12") (pin "2") (pinfunction "S_2") (pintype "passive"))
      (node (ref "Q13") (pin "2") (pinfunction "S_2") (pintype "passive"))
      (node (ref "Q17") (pin "2") (pinfunction "S_2") (pintype "passive"))
      (node (ref "Q18") (pin "2") (pinfunction "S_2") (pintype "passive"))
      (node (ref "Q19") (pin "2") (pinfunction "S_2") (pintype "passive"))
      (node (ref "Q5") (pin "2") (pinfunction "S_2") (pintype "passive"))
      (node (ref "Q6") (pin "2") (pinfunction "S_2") (pintype "passive"))
      (node (ref "Q7") (pin "2") (pinfunction "S_2") (pintype "passive"))
      (node (ref "R13") (pin "2") (pinfunction "2_2") (pintype "passive"))
      (node (ref "R14") (pin "2") (pinfunction "2_2") (pintype "passive"))
      (node (ref "R15") (pin "2") (pinfunction "2_2") (pintype "passive"))
      (node (ref "R25") (pin "2") (pinfunction "2_2") (pintype "passive"))
      (node (ref "R26") (pin "2") (pinfunction "2_2") (pintype "passive"))
      (node (ref "R27") (pin "2") (pinfunction "2_2") (pintype "passive"))
      (node (ref "R37") (pin "2") (pinfunction "2_2") (pintype "passive"))
      (node (ref "R38") (pin "2") (pinfunction "2_2") (pintype "passive"))
      (node (ref "R39") (pin "2") (pinfunction "2_2") (pintype "passive"))
      (node (ref "SJ1") (pin "2") (pinfunction "2_2") (pintype "passive"))
      (node (ref "SJ2") (pin "3") (pinfunction "3_3") (pintype "passive"))
      (node (ref "X18") (pin "1") (pinfunction "S_1") (pintype "passive"))
      (node (ref "X18") (pin "2") (pinfunction "S_2") (pintype "passive"))
      (node (ref "X19") (pin "1") (pinfunction "S_1") (pintype "passive"))
      (node (ref "X19") (pin "2") (pinfunction "S_2") (pintype "passive"))
      (node (ref "X20") (pin "1") (pinfunction "S_1") (pintype "passive"))
      (node (ref "X20") (pin "2") (pinfunction "S_2") (pintype "passive"))
      (node (ref "X21") (pin "1") (pinfunction "S_1") (pintype "passive"))
      (node (ref "X21") (pin "2") (pinfunction "S_2") (pintype "passive"))
    )
    (net (code "5") (name "A") (class "Default")
      (node (ref "Q20") (pin "3") (pinfunction "D_3") (pintype "bidirectional"))
      (node (ref "X10") (pin "5") (pinfunction "S_5") (pintype "passive"))
      (node (ref "X11") (pin "5") (pinfunction "S_5") (pintype "passive"))
      (node (ref "X12") (pin "5") (pinfunction "S_5") (pintype "passive"))
      (node (ref "X13") (pin "5") (pinfunction "S_5") (pintype "passive"))
      (node (ref "X14") (pin "5") (pinfunction "S_5") (pintype "passive"))
      (node (ref "X6") (pin "5") (pinfunction "S_5") (pintype "passive"))
      (node (ref "X7") (pin "5") (pinfunction "S_5") (pintype "passive"))
      (node (ref "X8") (pin "5") (pinfunction "S_5") (pintype "passive"))
      (node (ref "X9") (pin "5") (pinfunction "S_5") (pintype "passive"))
    )
    (net (code "6") (name "ADSOUND+") (class "Default")
      (node (ref "SJ4") (pin "1") (pinfunction "1_1") (pintype "passive"))
      (node (ref "U3") (pin "5") (pinfunction "OUT+_5") (pintype "bidirectional"))
    )
    (net (code "7") (name "ADSOUND-") (class "Default")
      (node (ref "SJ5") (pin "3") (pinfunction "3_3") (pintype "passive"))
      (node (ref "U3") (pin "8") (pinfunction "OUT-_8") (pintype "bidirectional"))
    )
    (net (code "8") (name "AN1") (class "Default")
      (node (ref "IC1") (pin "7") (pinfunction "QH_7") (pintype "tri_state"))
      (node (ref "R7") (pin "1") (pinfunction "1_1") (pintype "passive"))
    )
    (net (code "9") (name "AN2") (class "Default")
      (node (ref "IC2") (pin "15") (pinfunction "QA_15") (pintype "tri_state"))
      (node (ref "R19") (pin "1") (pinfunction "1_1") (pintype "passive"))
    )
    (net (code "10") (name "AN3") (class "Default")
      (node (ref "IC2") (pin "1") (pinfunction "QB_1") (pintype "tri_state"))
      (node (ref "R31") (pin "1") (pinfunction "1_1") (pintype "passive"))
    )
    (net (code "11") (name "AN4") (class "Default")
      (node (ref "IC2") (pin "2") (pinfunction "QC_2") (pintype "tri_state"))
      (node (ref "R8") (pin "1") (pinfunction "1_1") (pintype "passive"))
    )
    (net (code "12") (name "AN5") (class "Default")
      (node (ref "IC2") (pin "3") (pinfunction "QD_3") (pintype "tri_state"))
      (node (ref "R20") (pin "1") (pinfunction "1_1") (pintype "passive"))
    )
    (net (code "13") (name "AN6") (class "Default")
      (node (ref "IC2") (pin "4") (pinfunction "QE_4") (pintype "tri_state"))
      (node (ref "R32") (pin "1") (pinfunction "1_1") (pintype "passive"))
    )
    (net (code "14") (name "AN7") (class "Default")
      (node (ref "IC2") (pin "5") (pinfunction "QF_5") (pintype "tri_state"))
      (node (ref "R9") (pin "1") (pinfunction "1_1") (pintype "passive"))
    )
    (net (code "15") (name "AN8") (class "Default")
      (node (ref "IC2") (pin "6") (pinfunction "QG_6") (pintype "tri_state"))
      (node (ref "R21") (pin "1") (pinfunction "1_1") (pintype "passive"))
    )
    (net (code "16") (name "AN9") (class "Default")
      (node (ref "IC2") (pin "7") (pinfunction "QH_7") (pintype "tri_state"))
      (node (ref "R33") (pin "1") (pinfunction "1_1") (pintype "passive"))
    )
    (net (code "17") (name "B") (class "Default")
      (node (ref "Q21") (pin "3") (pinfunction "D_3") (pintype "bidirectional"))
      (node (ref "X10") (pin "6") (pinfunction "S_6") (pintype "passive"))
      (node (ref "X11") (pin "6") (pinfunction "S_6") (pintype "passive"))
      (node (ref "X12") (pin "6") (pinfunction "S_6") (pintype "passive"))
      (node (ref "X13") (pin "6") (pinfunction "S_6") (pintype "passive"))
      (node (ref "X14") (pin "6") (pinfunction "S_6") (pintype "passive"))
      (node (ref "X6") (pin "6") (pinfunction "S_6") (pintype "passive"))
      (node (ref "X7") (pin "6") (pinfunction "S_6") (pintype "passive"))
      (node (ref "X8") (pin "6") (pinfunction "S_6") (pintype "passive"))
      (node (ref "X9") (pin "6") (pinfunction "S_6") (pintype "passive"))
    )
    (net (code "18") (name "B_COL_0") (class "Default")
      (node (ref "U1") (pin "32") (pinfunction "PD2_32") (pintype "bidirectional"))
      (node (ref "X1") (pin "4") (pinfunction "S_4") (pintype "passive"))
      (node (ref "X2") (pin "4") (pinfunction "S_4") (pintype "passive"))
    )
    (net (code "19") (name "B_COL_1") (class "Default")
      (node (ref "U1") (pin "1") (pinfunction "PD3_1") (pintype "bidirectional"))
      (node (ref "X1") (pin "5") (pinfunction "S_5") (pintype "passive"))
      (node (ref "X2") (pin "5") (pinfunction "S_5") (pintype "passive"))
    )
    (net (code "20") (name "B_COL_2") (class "Default")
      (node (ref "U1") (pin "2") (pinfunction "PD4_2") (pintype "bidirectional"))
      (node (ref "X1") (pin "6") (pinfunction "S_6") (pintype "passive"))
      (node (ref "X2") (pin "6") (pinfunction "S_6") (pintype "passive"))
    )
    (net (code "21") (name "B_COL_3") (class "Default")
      (node (ref "U1") (pin "9") (pinfunction "PD5_9") (pintype "bidirectional"))
      (node (ref "X4") (pin "4") (pinfunction "S_4") (pintype "passive"))
      (node (ref "X5") (pin "4") (pinfunction "S_4") (pintype "passive"))
    )
    (net (code "22") (name "B_COL_4") (class "Default")
      (node (ref "U1") (pin "10") (pinfunction "PD6_10") (pintype "bidirectional"))
      (node (ref "X4") (pin "5") (pinfunction "S_5") (pintype "passive"))
      (node (ref "X5") (pin "5") (pinfunction "S_5") (pintype "passive"))
    )
    (net (code "23") (name "B_COL_5") (class "Default")
      (node (ref "U1") (pin "11") (pinfunction "PD7_11") (pintype "bidirectional"))
      (node (ref "X4") (pin "6") (pinfunction "S_6") (pintype "passive"))
      (node (ref "X5") (pin "6") (pinfunction "S_6") (pintype "passive"))
    )
    (net (code "24") (name "B_ROW_0") (class "Default")
      (node (ref "U1") (pin "23") (pinfunction "PC0_23") (pintype "bidirectional"))
      (node (ref "X1") (pin "1") (pinfunction "S_1") (pintype "passive"))
      (node (ref "X4") (pin "1") (pinfunction "S_1") (pintype "passive"))
    )
    (net (code "25") (name "B_ROW_1") (class "Default")
      (node (ref "U1") (pin "24") (pinfunction "PC1_24") (pintype "bidirectional"))
      (node (ref "X1") (pin "2") (pinfunction "S_2") (pintype "passive"))
      (node (ref "X4") (pin "2") (pinfunction "S_2") (pintype "passive"))
    )
    (net (code "26") (name "B_ROW_2") (class "Default")
      (node (ref "U1") (pin "25") (pinfunction "PC2_25") (pintype "bidirectional"))
      (node (ref "X1") (pin "3") (pinfunction "S_3") (pintype "passive"))
      (node (ref "X4") (pin "3") (pinfunction "S_3") (pintype "passive"))
    )
    (net (code "27") (name "B_ROW_3") (class "Default")
      (node (ref "U1") (pin "26") (pinfunction "PC3_26") (pintype "bidirectional"))
      (node (ref "X2") (pin "1") (pinfunction "S_1") (pintype "passive"))
      (node (ref "X5") (pin "1") (pinfunction "S_1") (pintype "passive"))
    )
    (net (code "28") (name "B_ROW_4") (class "Default")
      (node (ref "U1") (pin "27") (pinfunction "PC4_27") (pintype "bidirectional"))
      (node (ref "X2") (pin "2") (pinfunction "S_2") (pintype "passive"))
      (node (ref "X5") (pin "2") (pinfunction "S_2") (pintype "passive"))
    )
    (net (code "29") (name "B_ROW_5") (class "Default")
      (node (ref "U1") (pin "28") (pinfunction "PC5_28") (pintype "bidirectional"))
      (node (ref "X2") (pin "3") (pinfunction "S_3") (pintype "passive"))
      (node (ref "X5") (pin "3") (pinfunction "S_3") (pintype "passive"))
    )
    (net (code "30") (name "C") (class "Default")
      (node (ref "Q22") (pin "3") (pinfunction "D_3") (pintype "bidirectional"))
      (node (ref "X10") (pin "7") (pinfunction "S_7") (pintype "passive"))
      (node (ref "X11") (pin "7") (pinfunction "S_7") (pintype "passive"))
      (node (ref "X12") (pin "7") (pinfunction "S_7") (pintype "passive"))
      (node (ref "X13") (pin "7") (pinfunction "S_7") (pintype "passive"))
      (node (ref "X14") (pin "7") (pinfunction "S_7") (pintype "passive"))
      (node (ref "X6") (pin "7") (pinfunction "S_7") (pintype "passive"))
      (node (ref "X7") (pin "7") (pinfunction "S_7") (pintype "passive"))
      (node (ref "X8") (pin "7") (pinfunction "S_7") (pintype "passive"))
      (node (ref "X9") (pin "7") (pinfunction "S_7") (pintype "passive"))
    )
    (net (code "31") (name "D") (class "Default")
      (node (ref "Q23") (pin "3") (pinfunction "D_3") (pintype "bidirectional"))
      (node (ref "X10") (pin "1") (pinfunction "S_1") (pintype "passive"))
      (node (ref "X11") (pin "1") (pinfunction "S_1") (pintype "passive"))
      (node (ref "X12") (pin "1") (pinfunction "S_1") (pintype "passive"))
      (node (ref "X13") (pin "1") (pinfunction "S_1") (pintype "passive"))
      (node (ref "X14") (pin "1") (pinfunction "S_1") (pintype "passive"))
      (node (ref "X6") (pin "1") (pinfunction "S_1") (pintype "passive"))
      (node (ref "X7") (pin "1") (pinfunction "S_1") (pintype "passive"))
      (node (ref "X8") (pin "1") (pinfunction "S_1") (pintype "passive"))
      (node (ref "X9") (pin "1") (pinfunction "S_1") (pintype "passive"))
    )
    (net (code "32") (name "D+") (class "Default")
      (node (ref "JP5") (pin "3") (pinfunction "3_3") (pintype "passive"))
      (node (ref "R58") (pin "1") (pinfunction "1_1") (pintype "passive"))
      (node (ref "R59") (pin "2") (pinfunction "2_2") (pintype "passive"))
      (node (ref "R60") (pin "2") (pinfunction "2_2") (pintype "passive"))
      (node (ref "U$1") (pin "P$3") (pinfunction "D+_P$3") (pintype "bidirectional"))
    )
    (net (code "33") (name "D-") (class "Default")
      (node (ref "JP5") (pin "2") (pinfunction "2_2") (pintype "passive"))
      (node (ref "R61") (pin "2") (pinfunction "2_2") (pintype "passive"))
      (node (ref "R62") (pin "1") (pinfunction "1_1") (pintype "passive"))
      (node (ref "R63") (pin "1") (pinfunction "1_1") (pintype "passive"))
      (node (ref "U$1") (pin "P$2") (pinfunction "D-_P$2") (pintype "bidirectional"))
    )
    (net (code "34") (name "DTR") (class "Default")
      (node (ref "C1") (pin "2") (pinfunction "2_2") (pintype "passive"))
      (node (ref "J1") (pin "DTR") (pinfunction "1_DTR") (pintype "passive"))
    )
    (net (code "35") (name "E") (class "Default")
      (node (ref "Q24") (pin "3") (pinfunction "D_3") (pintype "bidirectional"))
      (node (ref "X10") (pin "2") (pinfunction "S_2") (pintype "passive"))
      (node (ref "X11") (pin "2") (pinfunction "S_2") (pintype "passive"))
      (node (ref "X12") (pin "2") (pinfunction "S_2") (pintype "passive"))
      (node (ref "X13") (pin "2") (pinfunction "S_2") (pintype "passive"))
      (node (ref "X14") (pin "2") (pinfunction "S_2") (pintype "passive"))
      (node (ref "X6") (pin "2") (pinfunction "S_2") (pintype "passive"))
      (node (ref "X7") (pin "2") (pinfunction "S_2") (pintype "passive"))
      (node (ref "X8") (pin "2") (pinfunction "S_2") (pintype "passive"))
      (node (ref "X9") (pin "2") (pinfunction "S_2") (pintype "passive"))
    )
    (net (code "36") (name "F") (class "Default")
      (node (ref "Q25") (pin "3") (pinfunction "D_3") (pintype "bidirectional"))
      (node (ref "X10") (pin "4") (pinfunction "S_4") (pintype "passive"))
      (node (ref "X11") (pin "4") (pinfunction "S_4") (pintype "passive"))
      (node (ref "X12") (pin "4") (pinfunction "S_4") (pintype "passive"))
      (node (ref "X13") (pin "4") (pinfunction "S_4") (pintype "passive"))
      (node (ref "X14") (pin "4") (pinfunction "S_4") (pintype "passive"))
      (node (ref "X6") (pin "4") (pinfunction "S_4") (pintype "passive"))
      (node (ref "X7") (pin "4") (pinfunction "S_4") (pintype "passive"))
      (node (ref "X8") (pin "4") (pinfunction "S_4") (pintype "passive"))
      (node (ref "X9") (pin "4") (pinfunction "S_4") (pintype "passive"))
    )
    (net (code "37") (name "FTDIRX") (class "Default")
      (node (ref "J1") (pin "TXO") (pinfunction "3_TXO") (pintype "passive"))
      (node (ref "JP1") (pin "2") (pinfunction "2_2") (pintype "passive"))
    )
    (net (code "38") (name "FTDITX") (class "Default")
      (node (ref "J1") (pin "RXI") (pinfunction "2_RXI") (pintype "passive"))
      (node (ref "JP2") (pin "2") (pinfunction "2_2") (pintype "passive"))
    )
    (net (code "39") (name "G") (class "Default")
      (node (ref "Q26") (pin "3") (pinfunction "D_3") (pintype "bidirectional"))
      (node (ref "X10") (pin "3") (pinfunction "S_3") (pintype "passive"))
      (node (ref "X11") (pin "3") (pinfunction "S_3") (pintype "passive"))
      (node (ref "X12") (pin "3") (pinfunction "S_3") (pintype "passive"))
      (node (ref "X13") (pin "3") (pinfunction "S_3") (pintype "passive"))
      (node (ref "X14") (pin "3") (pinfunction "S_3") (pintype "passive"))
      (node (ref "X6") (pin "3") (pinfunction "S_3") (pintype "passive"))
      (node (ref "X7") (pin "3") (pinfunction "S_3") (pintype "passive"))
      (node (ref "X8") (pin "3") (pinfunction "S_3") (pintype "passive"))
      (node (ref "X9") (pin "3") (pinfunction "S_3") (pintype "passive"))
    )
    (net (code "40") (name "GND") (class "Default")
      (node (ref "C10") (pin "-") (pinfunction "-_-") (pintype "passive"))
      (node (ref "C11") (pin "2") (pinfunction "2_2") (pintype "passive"))
      (node (ref "C13") (pin "1") (pinfunction "1_1") (pintype "passive"))
      (node (ref "C14") (pin "1") (pinfunction "1_1") (pintype "passive"))
      (node (ref "C15") (pin "2") (pinfunction "2_2") (pintype "passive"))
      (node (ref "C16") (pin "-") (pinfunction "-_-") (pintype "passive"))
      (node (ref "C17") (pin "-") (pinfunction "-_-") (pintype "passive"))
      (node (ref "C2") (pin "1") (pinfunction "1_1") (pintype "passive"))
      (node (ref "C3") (pin "1") (pinfunction "1_1") (pintype "passive"))
      (node (ref "C4") (pin "1") (pinfunction "1_1") (pintype "passive"))
      (node (ref "C5") (pin "1") (pinfunction "1_1") (pintype "passive"))
      (node (ref "C6") (pin "2") (pinfunction "2_2") (pintype "passive"))
      (node (ref "C7") (pin "2") (pinfunction "2_2") (pintype "passive"))
      (node (ref "C9") (pin "1") (pinfunction "1_1") (pintype "passive"))
      (node (ref "D1") (pin "A") (pinfunction "A_A") (pintype "passive"))
      (node (ref "IC1") (pin "8") (pinfunction "GND_8") (pintype "power_in"))
      (node (ref "IC2") (pin "8") (pinfunction "GND_8") (pintype "power_in"))
      (node (ref "IC3") (pin "3") (pinfunction "GND_3") (pintype "power_in"))
      (node (ref "IC3") (pin "6") (pinfunction "GND_6") (pintype "power_in"))
      (node (ref "ISP1") (pin "6") (pinfunction "GND_6") (pintype "power_in"))
      (node (ref "J1") (pin "CTS") (pinfunction "5_CTS") (pintype "passive"))
      (node (ref "J1") (pin "GND") (pinfunction "6_GND") (pintype "passive"))
      (node (ref "JP10") (pin "3") (pinfunction "3_3") (pintype "passive"))
      (node (ref "JP5") (pin "5") (pinfunction "5_5") (pintype "passive"))
      (node (ref "JP6") (pin "1") (pinfunction "1_1") (pintype "passive"))
      (node (ref "JP6") (pin "2") (pinfunction "2_2") (pintype "passive"))
      (node (ref "JP6") (pin "3") (pinfunction "3_3") (pintype "passive"))
      (node (ref "JP6") (pin "4") (pinfunction "4_4") (pintype "passive"))
      (node (ref "Q10") (pin "2") (pinfunction "S_2") (pintype "bidirectional"))
      (node (ref "Q14") (pin "2") (pinfunction "S_2") (pintype "bidirectional"))
      (node (ref "Q15") (pin "2") (pinfunction "S_2") (pintype "bidirectional"))
      (node (ref "Q16") (pin "2") (pinfunction "S_2") (pintype "bidirectional"))
      (node (ref "Q2") (pin "2") (pinfunction "S_2") (pintype "bidirectional"))
      (node (ref "Q20") (pin "2") (pinfunction "S_2") (pintype "bidirectional"))
      (node (ref "Q21") (pin "2") (pinfunction "S_2") (pintype "bidirectional"))
      (node (ref "Q22") (pin "2") (pinfunction "S_2") (pintype "bidirectional"))
      (node (ref "Q23") (pin "2") (pinfunction "S_2") (pintype "bidirectional"))
      (node (ref "Q24") (pin "2") (pinfunction "S_2") (pintype "bidirectional"))
      (node (ref "Q25") (pin "2") (pinfunction "S_2") (pintype "bidirectional"))
      (node (ref "Q26") (pin "2") (pinfunction "S_2") (pintype "bidirectional"))
      (node (ref "Q3") (pin "2") (pinfunction "S_2") (pintype "bidirectional"))
      (node (ref "Q4") (pin "2") (pinfunction "S_2") (pintype "bidirectional"))
      (node (ref "Q8") (pin "2") (pinfunction "S_2") (pintype "bidirectional"))
      (node (ref "Q9") (pin "2") (pinfunction "S_2") (pintype "bidirectional"))
      (node (ref "R10") (pin "1") (pinfunction "1_1") (pintype "passive"))
      (node (ref "R11") (pin "1") (pinfunction "1_1") (pintype "passive"))
      (node (ref "R12") (pin "1") (pinfunction "1_1") (pintype "passive"))
      (node (ref "R16") (pin "1") (pinfunction "1_1") (pintype "passive"))
      (node (ref "R17") (pin "1") (pinfunction "1_1") (pintype "passive"))
      (node (ref "R18") (pin "1") (pinfunction "1_1") (pintype "passive"))
      (node (ref "R22") (pin "1") (pinfunction "1_1") (pintype "passive"))
      (node (ref "R23") (pin "1") (pinfunction "1_1") (pintype "passive"))
      (node (ref "R24") (pin "1") (pinfunction "1_1") (pintype "passive"))
      (node (ref "R28") (pin "1") (pinfunction "1_1") (pintype "passive"))
      (node (ref "R29") (pin "1") (pinfunction "1_1") (pintype "passive"))
      (node (ref "R3") (pin "1") (pinfunction "1_1") (pintype "passive"))
      (node (ref "R30") (pin "1") (pinfunction "1_1") (pintype "passive"))
      (node (ref "R34") (pin "1") (pinfunction "1_1") (pintype "passive"))
      (node (ref "R35") (pin "1") (pinfunction "1_1") (pintype "passive"))
      (node (ref "R36") (pin "1") (pinfunction "1_1") (pintype "passive"))
      (node (ref "R40") (pin "1") (pinfunction "1_1") (pintype "passive"))
      (node (ref "R41") (pin "1") (pinfunction "1_1") (pintype "passive"))
      (node (ref "R42") (pin "1") (pinfunction "1_1") (pintype "passive"))
      (node (ref "R48") (pin "1") (pinfunction "1_1") (pintype "passive"))
      (node (ref "R49") (pin "1") (pinfunction "1_1") (pintype "passive"))
      (node (ref "R50") (pin "1") (pinfunction "1_1") (pintype "passive"))
      (node (ref "R51") (pin "1") (pinfunction "1_1") (pintype "passive"))
      (node (ref "R52") (pin "1") (pinfunction "1_1") (pintype "passive"))
      (node (ref "R55") (pin "1") (pinfunction "1_1") (pintype "passive"))
      (node (ref "R56") (pin "1") (pinfunction "1_1") (pintype "passive"))
      (node (ref "R57") (pin "1") (pinfunction "1_1") (pintype "passive"))
      (node (ref "R59") (pin "1") (pinfunction "1_1") (pintype "passive"))
      (node (ref "R62") (pin "2") (pinfunction "2_2") (pintype "passive"))
      (node (ref "RESET") (pin "1") (pinfunction "A1_1") (pintype "bidirectional"))
      (node (ref "SJ2") (pin "1") (pinfunction "1_1") (pintype "passive"))
      (node (ref "SJ5") (pin "1") (pinfunction "1_1") (pintype "passive"))
      (node (ref "U$1") (pin "P$5") (pinfunction "GND_P$5") (pintype "bidirectional"))
      (node (ref "U$1") (pin "P$6") (pinfunction "GND_P$6") (pintype "bidirectional"))
      (node (ref "U$1") (pin "P$8") (pinfunction "GND_P$8") (pintype "bidirectional"))
      (node (ref "U1") (pin "21") (pinfunction "GND_21") (pintype "power_in"))
      (node (ref "U1") (pin "5") (pinfunction "GND_5") (pintype "power_in"))
      (node (ref "U2") (pin "10") (pinfunction "GND_10") (pintype "bidirectional"))
      (node (ref "U2") (pin "11") (pinfunction "GND_11") (pintype "bidirectional"))
      (node (ref "U2") (pin "12") (pinfunction "GND_12") (pintype "bidirectional"))
      (node (ref "U2") (pin "3") (pinfunction "GND_3") (pintype "bidirectional"))
      (node (ref "U2") (pin "4") (pinfunction "GND_4") (pintype "bidirectional"))
      (node (ref "U2") (pin "5") (pinfunction "GND_5") (pintype "bidirectional"))
      (node (ref "U2") (pin "6") (pinfunction "IN-_6") (pintype "bidirectional"))
      (node (ref "U2") (pin "7") (pinfunction "GND_7") (pintype "bidirectional"))
      (node (ref "U3") (pin "7") (pinfunction "GND_7") (pintype "bidirectional"))
      (node (ref "U4") (pin "1") (pinfunction "GND_1") (pintype "power_in"))
      (node (ref "U4") (pin "15") (pinfunction "INDEP_15") (pintype "bidirectional"))
      (node (ref "U4") (pin "17") (pinfunction "VSS_17") (pintype "power_in"))
      (node (ref "U4") (pin "5") (pinfunction "VSS_5") (pintype "power_in"))
      (node (ref "U4") (pin "7") (pinfunction "RESET_7") (pintype "bidirectional"))
      (node (ref "U4") (pin "8") (pinfunction "DIS_8") (pintype "bidirectional"))
      (node (ref "X22") (pin "1") (pinfunction "S_1") (pintype "passive"))
      (node (ref "X22") (pin "2") (pinfunction "S_2") (pintype "passive"))
      (node (ref "X22") (pin "3") (pinfunction "S_3") (pintype "passive"))
      (node (ref "X23") (pin "1") (pinfunction "S_1") (pintype "passive"))
      (node (ref "X23") (pin "2") (pinfunction "S_2") (pintype "passive"))
      (node (ref "X23") (pin "3") (pinfunction "S_3") (pintype "passive"))
      (node (ref "X24") (pin "1") (pinfunction "S_1") (pintype "passive"))
      (node (ref "X24") (pin "2") (pinfunction "S_2") (pintype "passive"))
      (node (ref "X24") (pin "3") (pinfunction "S_3") (pintype "passive"))
      (node (ref "X25") (pin "1") (pinfunction "S_1") (pintype "passive"))
      (node (ref "X25") (pin "2") (pinfunction "S_2") (pintype "passive"))
      (node (ref "X25") (pin "3") (pinfunction "S_3") (pintype "passive"))
      (node (ref "X3") (pin "7") (pinfunction "S_7") (pintype "passive"))
    )
    (net (code "41") (name "LED_B") (class "Default")
      (node (ref "IC1") (pin "10") (pinfunction "SCL_10") (pintype "input"))
      (node (ref "IC2") (pin "10") (pinfunction "SCL_10") (pintype "input"))
      (node (ref "R2") (pin "1") (pinfunction "1_1") (pintype "passive"))
      (node (ref "U1") (pin "22") (pinfunction "PE3_22") (pintype "bidirectional"))
      (node (ref "X3") (pin "5") (pinfunction "S_5") (pintype "passive"))
    )
    (net (code "42") (name "LED_D_OUT") (class "Default")
      (node (ref "IC2") (pin "9") (pinfunction "QH*_9") (pintype "tri_state"))
      (node (ref "X3") (pin "2") (pinfunction "S_2") (pintype "passive"))
    )
    (net (code "43") (name "LED_L") (class "Default")
      (node (ref "IC1") (pin "12") (pinfunction "RCK_12") (pintype "input"))
      (node (ref "IC2") (pin "12") (pinfunction "RCK_12") (pintype "input"))
      (node (ref "R1") (pin "1") (pinfunction "1_1") (pintype "passive"))
      (node (ref "U1") (pin "12") (pinfunction "PB0_12") (pintype "bidirectional"))
      (node (ref "X3") (pin "4") (pinfunction "S_4") (pintype "passive"))
    )
    (net (code "44") (name "LED_O") (class "Default")
      (node (ref "IC1") (pin "13") (pinfunction "G_13") (pintype "input"))
      (node (ref "IC2") (pin "13") (pinfunction "G_13") (pintype "input"))
      (node (ref "R3") (pin "2") (pinfunction "2_2") (pintype "passive"))
      (node (ref "U1") (pin "19") (pinfunction "PE2_19") (pintype "bidirectional"))
      (node (ref "X3") (pin "6") (pinfunction "S_6") (pintype "passive"))
    )
    (net (code "45") (name "LMSOUND") (class "Default")
      (node (ref "C12") (pin "-") (pinfunction "-_-") (pintype "passive"))
      (node (ref "SJ4") (pin "3") (pinfunction "3_3") (pintype "passive"))
    )
    (net (code "46") (name "MISO") (class "Default")
      (node (ref "ISP1") (pin "1") (pinfunction "MISO_1") (pintype "input"))
      (node (ref "U1") (pin "16") (pinfunction "PB4_16") (pintype "bidirectional"))
      (node (ref "U4") (pin "14") (pinfunction "SDO_AD1_14") (pintype "bidirectional"))
    )
    (net (code "47") (name "MOSI") (class "Default")
      (node (ref "IC1") (pin "14") (pinfunction "SER_14") (pintype "input"))
      (node (ref "ISP1") (pin "4") (pinfunction "MOSI_4") (pintype "output"))
      (node (ref "U1") (pin "15") (pinfunction "PB3_15") (pintype "bidirectional"))
      (node (ref "U4") (pin "12") (pinfunction "SDI_SDA_12") (pintype "bidirectional"))
    )
    (net (code "48") (name "Net-(IC1A-QH*)") (class "Default")
      (node (ref "IC1") (pin "9") (pinfunction "QH*_9") (pintype "tri_state"))
      (node (ref "IC2") (pin "14") (pinfunction "SER_14") (pintype "input"))
    )
    (net (code "49") (name "Net-(IC3-EN)") (class "Default")
      (node (ref "IC3") (pin "5") (pinfunction "EN_5") (pintype "input"))
      (node (ref "SJ2") (pin "2") (pinfunction "2_2") (pintype "passive"))
    )
    (net (code "50") (name "Net-(IC3-FB)") (class "Default")
      (node (ref "C17") (pin "+") (pinfunction "+_+") (pintype "passive"))
      (node (ref "IC3") (pin "4") (pinfunction "FB_4") (pintype "input"))
      (node (ref "L1") (pin "P$2") (pinfunction "2_P$2") (pintype "passive"))
      (node (ref "SJ3") (pin "2") (pinfunction "2_2") (pintype "passive"))
    )
    (net (code "51") (name "Net-(IC3-OUT)") (class "Default")
      (node (ref "D1") (pin "C") (pinfunction "C_C") (pintype "passive"))
      (node (ref "IC3") (pin "2") (pinfunction "OUT_2") (pintype "output"))
      (node (ref "L1") (pin "P$1") (pinfunction "1_P$1") (pintype "passive"))
    )
    (net (code "52") (name "Net-(Q2-D)") (class "Default")
      (node (ref "Q2") (pin "3") (pinfunction "D_3") (pintype "bidirectional"))
      (node (ref "Q5") (pin "1") (pinfunction "G_1") (pintype "passive"))
      (node (ref "R13") (pin "1") (pinfunction "1_1") (pintype "passive"))
    )
    (net (code "53") (name "Net-(Q2-G)") (class "Default")
      (node (ref "Q2") (pin "1") (pinfunction "G_1") (pintype "bidirectional"))
      (node (ref "R10") (pin "2") (pinfunction "2_2") (pintype "passive"))
      (node (ref "R7") (pin "2") (pinfunction "2_2") (pintype "passive"))
    )
    (net (code "54") (name "Net-(Q3-D)") (class "Default")
      (node (ref "Q3") (pin "3") (pinfunction "D_3") (pintype "bidirectional"))
      (node (ref "Q6") (pin "1") (pinfunction "G_1") (pintype "passive"))
      (node (ref "R14") (pin "1") (pinfunction "1_1") (pintype "passive"))
    )
    (net (code "55") (name "Net-(Q3-G)") (class "Default")
      (node (ref "Q3") (pin "1") (pinfunction "G_1") (pintype "bidirectional"))
      (node (ref "R11") (pin "2") (pinfunction "2_2") (pintype "passive"))
      (node (ref "R8") (pin "2") (pinfunction "2_2") (pintype "passive"))
    )
    (net (code "56") (name "Net-(Q4-D)") (class "Default")
      (node (ref "Q4") (pin "3") (pinfunction "D_3") (pintype "bidirectional"))
      (node (ref "Q7") (pin "1") (pinfunction "G_1") (pintype "passive"))
      (node (ref "R15") (pin "1") (pinfunction "1_1") (pintype "passive"))
    )
    (net (code "57") (name "Net-(Q4-G)") (class "Default")
      (node (ref "Q4") (pin "1") (pinfunction "G_1") (pintype "bidirectional"))
      (node (ref "R12") (pin "2") (pinfunction "2_2") (pintype "passive"))
      (node (ref "R9") (pin "2") (pinfunction "2_2") (pintype "passive"))
    )
    (net (code "58") (name "Net-(Q8-G)") (class "Default")
      (node (ref "Q8") (pin "1") (pinfunction "G_1") (pintype "bidirectional"))
      (node (ref "R19") (pin "2") (pinfunction "2_2") (pintype "passive"))
      (node (ref "R22") (pin "2") (pinfunction "2_2") (pintype "passive"))
    )
    (net (code "59") (name "Net-(Q9-G)") (class "Default")
      (node (ref "Q9") (pin "1") (pinfunction "G_1") (pintype "bidirectional"))
      (node (ref "R20") (pin "2") (pinfunction "2_2") (pintype "passive"))
      (node (ref "R23") (pin "2") (pinfunction "2_2") (pintype "passive"))
    )
    (net (code "60") (name "Net-(Q10-D)") (class "Default")
      (node (ref "Q10") (pin "3") (pinfunction "D_3") (pintype "bidirectional"))
      (node (ref "Q13") (pin "1") (pinfunction "G_1") (pintype "passive"))
      (node (ref "R27") (pin "1") (pinfunction "1_1") (pintype "passive"))
    )
    (net (code "61") (name "Net-(Q10-G)") (class "Default")
      (node (ref "Q10") (pin "1") (pinfunction "G_1") (pintype "bidirectional"))
      (node (ref "R21") (pin "2") (pinfunction "2_2") (pintype "passive"))
      (node (ref "R24") (pin "2") (pinfunction "2_2") (pintype "passive"))
    )
    (net (code "62") (name "Net-(Q11-G)") (class "Default")
      (node (ref "Q11") (pin "1") (pinfunction "G_1") (pintype "passive"))
      (node (ref "Q8") (pin "3") (pinfunction "D_3") (pintype "bidirectional"))
      (node (ref "R25") (pin "1") (pinfunction "1_1") (pintype "passive"))
    )
    (net (code "63") (name "Net-(Q12-G)") (class "Default")
      (node (ref "Q12") (pin "1") (pinfunction "G_1") (pintype "passive"))
      (node (ref "Q9") (pin "3") (pinfunction "D_3") (pintype "bidirectional"))
      (node (ref "R26") (pin "1") (pinfunction "1_1") (pintype "passive"))
    )
    (net (code "64") (name "Net-(Q14-D)") (class "Default")
      (node (ref "Q14") (pin "3") (pinfunction "D_3") (pintype "bidirectional"))
      (node (ref "Q17") (pin "1") (pinfunction "G_1") (pintype "passive"))
      (node (ref "R37") (pin "1") (pinfunction "1_1") (pintype "passive"))
    )
    (net (code "65") (name "Net-(Q14-G)") (class "Default")
      (node (ref "Q14") (pin "1") (pinfunction "G_1") (pintype "bidirectional"))
      (node (ref "R31") (pin "2") (pinfunction "2_2") (pintype "passive"))
      (node (ref "R34") (pin "2") (pinfunction "2_2") (pintype "passive"))
    )
    (net (code "66") (name "Net-(Q15-D)") (class "Default")
      (node (ref "Q15") (pin "3") (pinfunction "D_3") (pintype "bidirectional"))
      (node (ref "Q18") (pin "1") (pinfunction "G_1") (pintype "passive"))
      (node (ref "R38") (pin "1") (pinfunction "1_1") (pintype "passive"))
    )
    (net (code "67") (name "Net-(Q15-G)") (class "Default")
      (node (ref "Q15") (pin "1") (pinfunction "G_1") (pintype "bidirectional"))
      (node (ref "R32") (pin "2") (pinfunction "2_2") (pintype "passive"))
      (node (ref "R35") (pin "2") (pinfunction "2_2") (pintype "passive"))
    )
    (net (code "68") (name "Net-(Q16-D)") (class "Default")
      (node (ref "Q16") (pin "3") (pinfunction "D_3") (pintype "bidirectional"))
      (node (ref "Q19") (pin "1") (pinfunction "G_1") (pintype "passive"))
      (node (ref "R39") (pin "1") (pinfunction "1_1") (pintype "passive"))
    )
    (net (code "69") (name "Net-(Q16-G)") (class "Default")
      (node (ref "Q16") (pin "1") (pinfunction "G_1") (pintype "bidirectional"))
      (node (ref "R33") (pin "2") (pinfunction "2_2") (pintype "passive"))
      (node (ref "R36") (pin "2") (pinfunction "2_2") (pintype "passive"))
    )
    (net (code "70") (name "Net-(Q20-G)") (class "Default")
      (node (ref "Q20") (pin "1") (pinfunction "G_1") (pintype "bidirectional"))
      (node (ref "R43") (pin "2") (pinfunction "2_2") (pintype "passive"))
      (node (ref "R48") (pin "2") (pinfunction "2_2") (pintype "passive"))
    )
    (net (code "71") (name "Net-(Q21-G)") (class "Default")
      (node (ref "Q21") (pin "1") (pinfunction "G_1") (pintype "bidirectional"))
      (node (ref "R44") (pin "2") (pinfunction "2_2") (pintype "passive"))
      (node (ref "R49") (pin "2") (pinfunction "2_2") (pintype "passive"))
    )
    (net (code "72") (name "Net-(Q22-G)") (class "Default")
      (node (ref "Q22") (pin "1") (pinfunction "G_1") (pintype "bidirectional"))
      (node (ref "R45") (pin "2") (pinfunction "2_2") (pintype "passive"))
      (node (ref "R50") (pin "2") (pinfunction "2_2") (pintype "passive"))
    )
    (net (code "73") (name "Net-(Q23-G)") (class "Default")
      (node (ref "Q23") (pin "1") (pinfunction "G_1") (pintype "bidirectional"))
      (node (ref "R46") (pin "2") (pinfunction "2_2") (pintype "passive"))
      (node (ref "R51") (pin "2") (pinfunction "2_2") (pintype "passive"))
    )
    (net (code "74") (name "Net-(Q24-G)") (class "Default")
      (node (ref "Q24") (pin "1") (pinfunction "G_1") (pintype "bidirectional"))
      (node (ref "R47") (pin "2") (pinfunction "2_2") (pintype "passive"))
      (node (ref "R52") (pin "2") (pinfunction "2_2") (pintype "passive"))
    )
    (net (code "75") (name "Net-(Q25-G)") (class "Default")
      (node (ref "Q25") (pin "1") (pinfunction "G_1") (pintype "bidirectional"))
      (node (ref "R53") (pin "2") (pinfunction "2_2") (pintype "passive"))
      (node (ref "R55") (pin "2") (pinfunction "2_2") (pintype "passive"))
    )
    (net (code "76") (name "Net-(Q26-G)") (class "Default")
      (node (ref "Q26") (pin "1") (pinfunction "G_1") (pintype "bidirectional"))
      (node (ref "R54") (pin "2") (pinfunction "2_2") (pintype "passive"))
      (node (ref "R56") (pin "2") (pinfunction "2_2") (pintype "passive"))
    )
    (net (code "77") (name "Net-(U$1-+5)") (class "Default")
      (node (ref "JP5") (pin "1") (pinfunction "1_1") (pintype "passive"))
      (node (ref "SJ1") (pin "1") (pinfunction "1_1") (pintype "passive"))
      (node (ref "U$1") (pin "P$1") (pinfunction "+5_P$1") (pintype "bidirectional"))
    )
    (net (code "78") (name "Net-(U$1-ID)") (class "Default")
      (node (ref "JP5") (pin "4") (pinfunction "4_4") (pintype "passive"))
      (node (ref "U$1") (pin "P$4") (pinfunction "ID_P$4") (pintype "bidirectional"))
    )
    (net (code "79") (name "Net-(U1-PB6{slash}XTAL1)") (class "Default")
      (node (ref "C2") (pin "2") (pinfunction "2_2") (pintype "passive"))
      (node (ref "Q1") (pin "1") (pinfunction "1_1") (pintype "passive"))
      (node (ref "U1") (pin "7") (pinfunction "PB6/XTAL1_7") (pintype "bidirectional"))
    )
    (net (code "80") (name "Net-(U1-PB7{slash}XTAL2)") (class "Default")
      (node (ref "C3") (pin "2") (pinfunction "2_2") (pintype "passive"))
      (node (ref "Q1") (pin "2") (pinfunction "2_2") (pintype "passive"))
      (node (ref "U1") (pin "8") (pinfunction "PB7/XTAL2_8") (pintype "bidirectional"))
    )
    (net (code "81") (name "Net-(U2-BYPASS)") (class "Default")
      (node (ref "C11") (pin "1") (pinfunction "1_1") (pintype "passive"))
      (node (ref "U2") (pin "1") (pinfunction "BYPASS_1") (pintype "bidirectional"))
    )
    (net (code "82") (name "Net-(U2-OUT)") (class "Default")
      (node (ref "C12") (pin "+") (pinfunction "+_+") (pintype "passive"))
      (node (ref "U2") (pin "8") (pinfunction "OUT_8") (pintype "bidirectional"))
    )
    (net (code "83") (name "Net-(U3-IN+)") (class "Default")
      (node (ref "C8") (pin "2") (pinfunction "2_2") (pintype "passive"))
      (node (ref "U3") (pin "3") (pinfunction "IN+_3") (pintype "bidirectional"))
    )
    (net (code "84") (name "Net-(U3-IN-)") (class "Default")
      (node (ref "C9") (pin "2") (pinfunction "2_2") (pintype "passive"))
      (node (ref "U3") (pin "4") (pinfunction "IN-_4") (pintype "bidirectional"))
    )
    (net (code "85") (name "Net-(U4-B)") (class "Default")
      (node (ref "R57") (pin "2") (pinfunction "2_2") (pintype "passive"))
      (node (ref "U4") (pin "4") (pinfunction "B_4") (pintype "bidirectional"))
    )
    (net (code "86") (name "Net-(X15B-KL)") (class "Default")
      (node (ref "X15") (pin "2") (pinfunction "KL_2") (pintype "passive"))
      (node (ref "X16") (pin "1") (pinfunction "KL_1") (pintype "passive"))
    )
    (net (code "87") (name "RX") (class "Default")
      (node (ref "JP1") (pin "3") (pinfunction "3_3") (pintype "passive"))
      (node (ref "JP2") (pin "1") (pinfunction "1_1") (pintype "passive"))
      (node (ref "U1") (pin "30") (pinfunction "PD0_30") (pintype "bidirectional"))
    )
    (net (code "88") (name "SCK") (class "Default")
      (node (ref "IC1") (pin "11") (pinfunction "SCK_11") (pintype "input"))
      (node (ref "IC2") (pin "11") (pinfunction "SCK_11") (pintype "input"))
      (node (ref "ISP1") (pin "3") (pinfunction "SCK_3") (pintype "output"))
      (node (ref "U1") (pin "17") (pinfunction "PB5_17") (pintype "bidirectional"))
      (node (ref "U4") (pin "11") (pinfunction "SCLK_SCL_11") (pintype "bidirectional"))
      (node (ref "X3") (pin "3") (pinfunction "S_3") (pintype "passive"))
    )
    (net (code "89") (name "SCORE0_1") (class "Default")
      (node (ref "Q5") (pin "3") (pinfunction "D_3") (pintype "passive"))
      (node (ref "R16") (pin "2") (pinfunction "2_2") (pintype "passive"))
      (node (ref "X6") (pin "8") (pinfunction "S_8") (pintype "passive"))
    )
    (net (code "90") (name "SCORE0_10") (class "Default")
      (node (ref "Q11") (pin "3") (pinfunction "D_3") (pintype "passive"))
      (node (ref "R28") (pin "2") (pinfunction "2_2") (pintype "passive"))
      (node (ref "X7") (pin "8") (pinfunction "S_8") (pintype "passive"))
    )
    (net (code "91") (name "SCORE0_100") (class "Default")
      (node (ref "Q17") (pin "3") (pinfunction "D_3") (pintype "passive"))
      (node (ref "R40") (pin "2") (pinfunction "2_2") (pintype "passive"))
      (node (ref "X8") (pin "8") (pinfunction "S_8") (pintype "passive"))
    )
    (net (code "92") (name "SCORE1_1") (class "Default")
      (node (ref "Q6") (pin "3") (pinfunction "D_3") (pintype "passive"))
      (node (ref "R17") (pin "2") (pinfunction "2_2") (pintype "passive"))
      (node (ref "X9") (pin "8") (pinfunction "S_8") (pintype "passive"))
    )
    (net (code "93") (name "SCORE1_10") (class "Default")
      (node (ref "Q12") (pin "3") (pinfunction "D_3") (pintype "passive"))
      (node (ref "R29") (pin "2") (pinfunction "2_2") (pintype "passive"))
      (node (ref "X10") (pin "8") (pinfunction "S_8") (pintype "passive"))
    )
    (net (code "94") (name "SCORE1_100") (class "Default")
      (node (ref "Q18") (pin "3") (pinfunction "D_3") (pintype "passive"))
      (node (ref "R41") (pin "2") (pinfunction "2_2") (pintype "passive"))
      (node (ref "X11") (pin "8") (pinfunction "S_8") (pintype "passive"))
    )
    (net (code "95") (name "SCORE2_1") (class "Default")
      (node (ref "Q7") (pin "3") (pinfunction "D_3") (pintype "passive"))
      (node (ref "R18") (pin "2") (pinfunction "2_2") (pintype "passive"))
      (node (ref "X12") (pin "8") (pinfunction "S_8") (pintype "passive"))
    )
    (net (code "96") (name "SCORE2_10") (class "Default")
      (node (ref "Q13") (pin "3") (pinfunction "D_3") (pintype "passive"))
      (node (ref "R30") (pin "2") (pinfunction "2_2") (pintype "passive"))
      (node (ref "X13") (pin "8") (pinfunction "S_8") (pintype "passive"))
    )
    (net (code "97") (name "SCORE2_100") (class "Default")
      (node (ref "Q19") (pin "3") (pinfunction "D_3") (pintype "passive"))
      (node (ref "R42") (pin "2") (pinfunction "2_2") (pintype "passive"))
      (node (ref "X14") (pin "8") (pinfunction "S_8") (pintype "passive"))
    )
    (net (code "98") (name "SIGA") (class "Default")
      (node (ref "IC1") (pin "15") (pinfunction "QA_15") (pintype "tri_state"))
      (node (ref "R43") (pin "1") (pinfunction "1_1") (pintype "passive"))
    )
    (net (code "99") (name "SIGB") (class "Default")
      (node (ref "IC1") (pin "1") (pinfunction "QB_1") (pintype "tri_state"))
      (node (ref "R44") (pin "1") (pinfunction "1_1") (pintype "passive"))
    )
    (net (code "100") (name "SIGC") (class "Default")
      (node (ref "IC1") (pin "2") (pinfunction "QC_2") (pintype "tri_state"))
      (node (ref "R45") (pin "1") (pinfunction "1_1") (pintype "passive"))
    )
    (net (code "101") (name "SIGD") (class "Default")
      (node (ref "IC1") (pin "3") (pinfunction "QD_3") (pintype "tri_state"))
      (node (ref "R46") (pin "1") (pinfunction "1_1") (pintype "passive"))
    )
    (net (code "102") (name "SIGE") (class "Default")
      (node (ref "IC1") (pin "4") (pinfunction "QE_4") (pintype "tri_state"))
      (node (ref "R47") (pin "1") (pinfunction "1_1") (pintype "passive"))
    )
    (net (code "103") (name "SIGF") (class "Default")
      (node (ref "IC1") (pin "5") (pinfunction "QF_5") (pintype "tri_state"))
      (node (ref "R53") (pin "1") (pinfunction "1_1") (pintype "passive"))
    )
    (net (code "104") (name "SIGG") (class "Default")
      (node (ref "IC1") (pin "6") (pinfunction "QG_6") (pintype "tri_state"))
      (node (ref "R54") (pin "1") (pinfunction "1_1") (pintype "passive"))
    )
    (net (code "105") (name "SOUND+") (class "Default")
      (node (ref "SJ4") (pin "2") (pinfunction "2_2") (pintype "passive"))
      (node (ref "X15") (pin "1") (pinfunction "KL_1") (pintype "passive"))
    )
    (net (code "106") (name "SOUND-") (class "Default")
      (node (ref "SJ5") (pin "2") (pinfunction "2_2") (pintype "passive"))
      (node (ref "X16") (pin "2") (pinfunction "KL_2") (pintype "passive"))
    )
    (net (code "107") (name "SOUNDOUT") (class "Default")
      (node (ref "SJ6") (pin "2") (pinfunction "2_2") (pintype "passive"))
      (node (ref "U1") (pin "13") (pinfunction "PB1_13") (pintype "bidirectional"))
      (node (ref "U4") (pin "2") (pinfunction "A_2") (pintype "bidirectional"))
    )
    (net (code "108") (name "SOUND_ATND") (class "Default")
      (node (ref "C8") (pin "1") (pinfunction "1_1") (pintype "passive"))
      (node (ref "SJ6") (pin "1") (pinfunction "1_1") (pintype "passive"))
      (node (ref "U2") (pin "2") (pinfunction "IN+_2") (pintype "bidirectional"))
      (node (ref "U4") (pin "3") (pinfunction "W_3") (pintype "bidirectional"))
    )
    (net (code "109") (name "SOUND_CS") (class "Default")
      (node (ref "R4") (pin "1") (pinfunction "1_1") (pintype "passive"))
      (node (ref "U1") (pin "14") (pinfunction "PB2_14") (pintype "bidirectional"))
      (node (ref "U4") (pin "6") (pinfunction "SY_AD0_6") (pintype "bidirectional"))
    )
    (net (code "110") (name "TX") (class "Default")
      (node (ref "JP1") (pin "1") (pinfunction "1_1") (pintype "passive"))
      (node (ref "JP2") (pin "3") (pinfunction "3_3") (pintype "passive"))
      (node (ref "U1") (pin "31") (pinfunction "PD1_31") (pintype "bidirectional"))
    )
    (net (code "111") (name "UCD+") (class "Default")
      (node (ref "R60") (pin "1") (pinfunction "1_1") (pintype "passive"))
      (node (ref "U1") (pin "6") (pinfunction "PE1_6") (pintype "bidirectional"))
    )
    (net (code "112") (name "UCD-") (class "Default")
      (node (ref "R63") (pin "2") (pinfunction "2_2") (pintype "passive"))
      (node (ref "U1") (pin "3") (pinfunction "PE0_3") (pintype "bidirectional"))
    )
    (net (code "113") (name "UC_RESET") (class "Default")
      (node (ref "C1") (pin "1") (pinfunction "1_1") (pintype "passive"))
      (node (ref "C5") (pin "2") (pinfunction "2_2") (pintype "passive"))
      (node (ref "ISP1") (pin "5") (pinfunction "RST_5") (pintype "output"))
      (node (ref "R6") (pin "1") (pinfunction "1_1") (pintype "passive"))
      (node (ref "RESET") (pin "3") (pinfunction "B1_3") (pintype "bidirectional"))
      (node (ref "U1") (pin "29") (pinfunction "PC6/RESET_29") (pintype "bidirectional"))
    )
    (net (code "114") (name "unconnected-(RESET-A2-Pad2)") (class "Default")
      (node (ref "RESET") (pin "2") (pinfunction "A2_2") (pintype "bidirectional"))
    )
    (net (code "115") (name "unconnected-(RESET-B2-Pad4)") (class "Default")
      (node (ref "RESET") (pin "4") (pinfunction "B2_4") (pintype "bidirectional"))
    )
  )
)
